# USBLCD_driver.net
KiCad netlist of a schematic drawn in Altium Designer
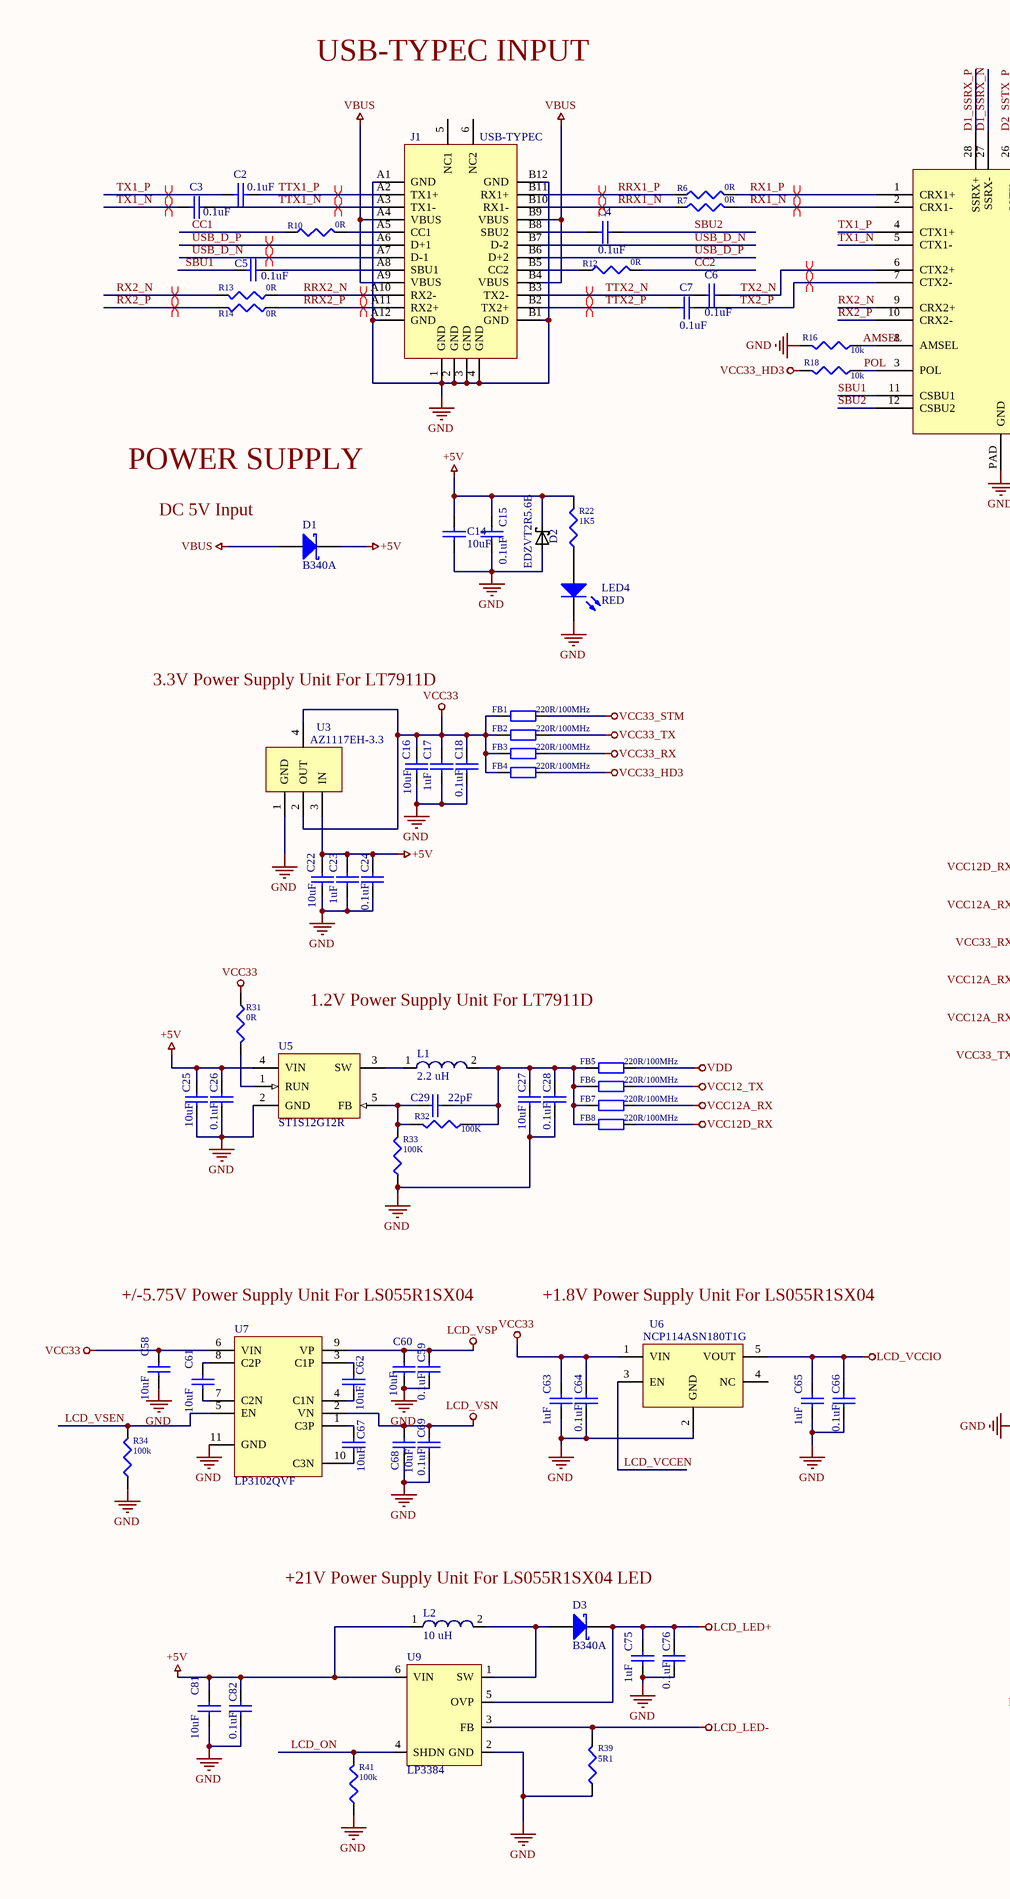
[diagram p0: USBLCD_driver.SchDoc, left]
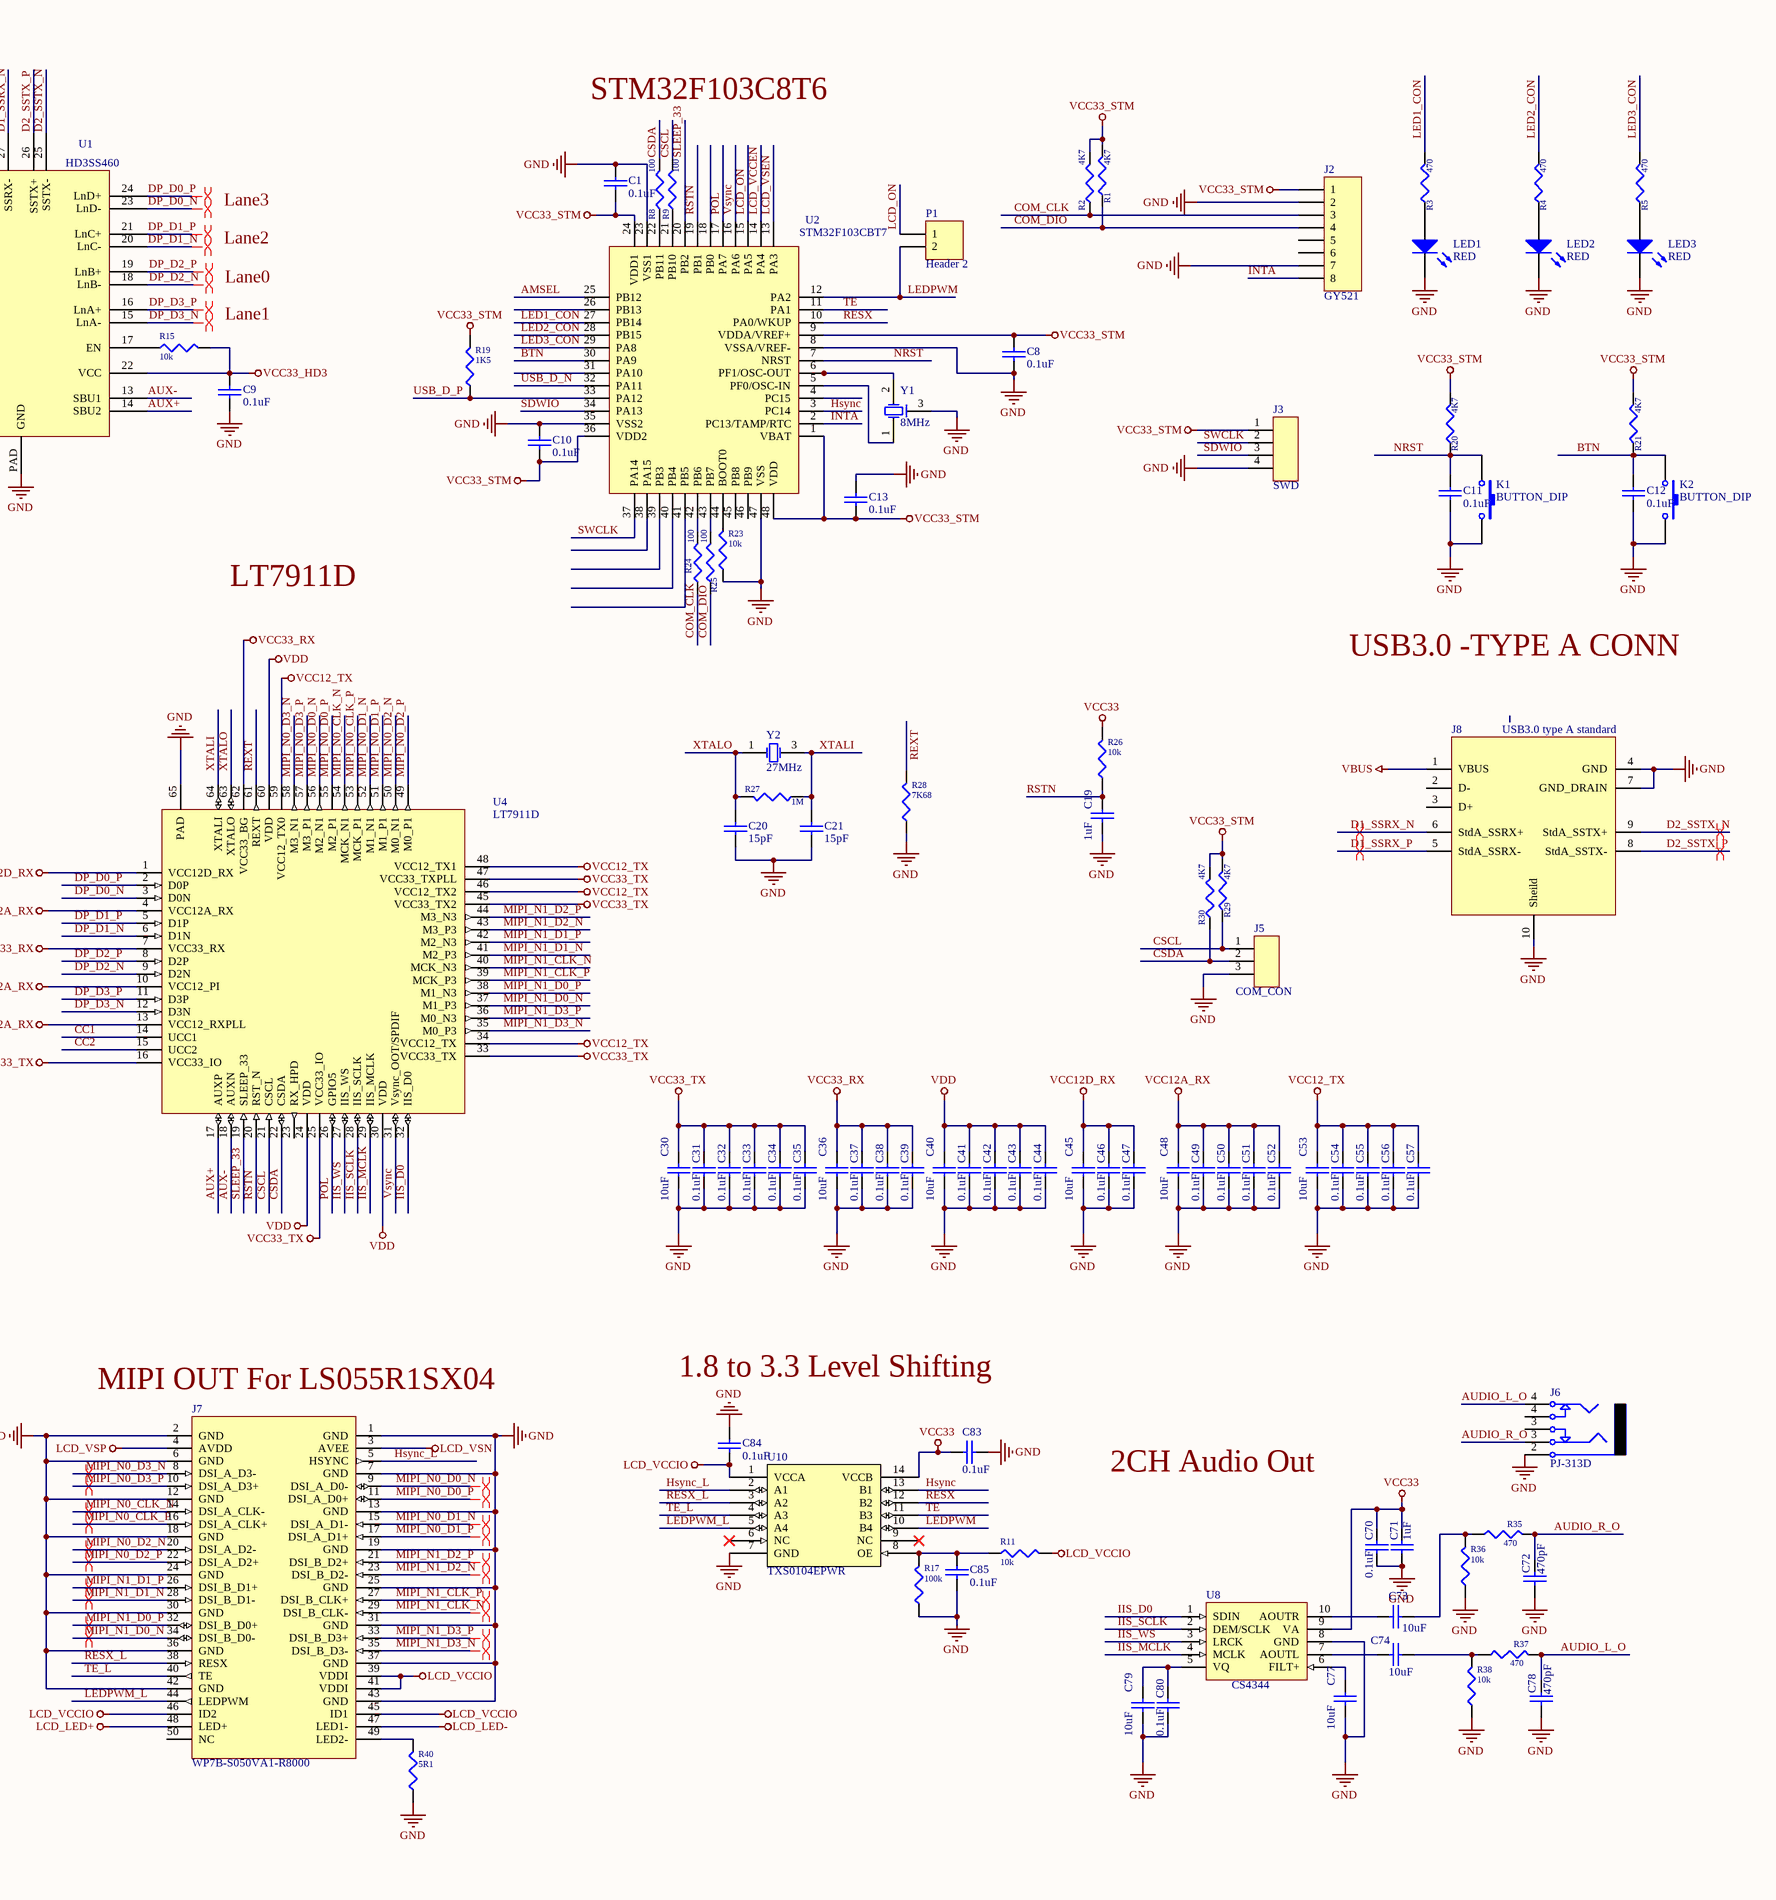
[diagram p1: USBLCD_driver.SchDoc, right]

(export (version "E")
  (design (tool "Eeschema 10.0.6"))
  (components
    (comp (ref "C1")
      (value "0.1uF")
      (footprint "CAPACITOR_SMD_0402")
      (description "CAP CER 0.1UF 16V X7R 0402")
      (fields
        (field (name "MANUFACTURER") "Murata Electronics North America")
        (field (name "MANUFACTURER PART NUMBER") "GRM155R71C104KA88D")
      )
      (libsource (lib "Maxium Referance Library for Watch") (part "CAP_0402_100n"))
    )
    (comp (ref "C2")
      (value "0.1uF")
      (footprint "CAPACITOR_SMD_0201")
      (description "CAP CER 0.1UF 10V X5R 0201")
      (fields
        (field (name "MANUFACTURER") "Murata Electronics North America")
        (field (name "MANUFACTURER PART NUMBER") "GRM033R61A104KE15D")
      )
      (libsource (lib "Maxium Referance Library for Watch") (part "CAP_0201_100n"))
    )
    (comp (ref "C3")
      (value "0.1uF")
      (footprint "CAPACITOR_SMD_0201")
      (description "CAP CER 0.1UF 10V X5R 0201")
      (fields
        (field (name "MANUFACTURER") "Murata Electronics North America")
        (field (name "MANUFACTURER PART NUMBER") "GRM033R61A104KE15D")
      )
      (libsource (lib "Maxium Referance Library for Watch") (part "CAP_0201_100n"))
    )
    (comp (ref "C4")
      (value "0.1uF")
      (footprint "CAPACITOR_SMD_0201")
      (description "CAP CER 0.1UF 10V X5R 0201")
      (fields
        (field (name "MANUFACTURER") "Murata Electronics North America")
        (field (name "MANUFACTURER PART NUMBER") "GRM033R61A104KE15D")
      )
      (libsource (lib "Maxium Referance Library for Watch") (part "CAP_0201_100n"))
    )
    (comp (ref "C5")
      (value "0.1uF")
      (footprint "CAPACITOR_SMD_0201")
      (description "CAP CER 0.1UF 10V X5R 0201")
      (fields
        (field (name "MANUFACTURER") "Murata Electronics North America")
        (field (name "MANUFACTURER PART NUMBER") "GRM033R61A104KE15D")
      )
      (libsource (lib "Maxium Referance Library for Watch") (part "CAP_0201_100n"))
    )
    (comp (ref "C6")
      (value "0.1uF")
      (footprint "CAPACITOR_SMD_0201")
      (description "CAP CER 0.1UF 10V X5R 0201")
      (fields
        (field (name "MANUFACTURER") "Murata Electronics North America")
        (field (name "MANUFACTURER PART NUMBER") "GRM033R61A104KE15D")
      )
      (libsource (lib "Maxium Referance Library for Watch") (part "CAP_0201_100n"))
    )
    (comp (ref "C7")
      (value "0.1uF")
      (footprint "CAPACITOR_SMD_0201")
      (description "CAP CER 0.1UF 10V X5R 0201")
      (fields
        (field (name "MANUFACTURER") "Murata Electronics North America")
        (field (name "MANUFACTURER PART NUMBER") "GRM033R61A104KE15D")
      )
      (libsource (lib "Maxium Referance Library for Watch") (part "CAP_0201_100n"))
    )
    (comp (ref "C8")
      (value "0.1uF")
      (footprint "CAPACITOR_SMD_0402")
      (description "CAP CER 0.1UF 16V X7R 0402")
      (fields
        (field (name "MANUFACTURER") "Murata Electronics North America")
        (field (name "MANUFACTURER PART NUMBER") "GRM155R71C104KA88D")
      )
      (libsource (lib "Maxium Referance Library for Watch") (part "CAP_0402_100n"))
    )
    (comp (ref "C9")
      (value "0.1uF")
      (footprint "CAPACITOR_SMD_0402")
      (description "CAP CER 0.1UF 16V X7R 0402")
      (fields
        (field (name "MANUFACTURER") "Murata Electronics North America")
        (field (name "MANUFACTURER PART NUMBER") "GRM155R71C104KA88D")
      )
      (libsource (lib "Maxium Referance Library for Watch") (part "CAP_0402_100n"))
    )
    (comp (ref "C10")
      (value "0.1uF")
      (footprint "CAPACITOR_SMD_0402")
      (description "CAP CER 0.1UF 16V X7R 0402")
      (fields
        (field (name "MANUFACTURER") "Murata Electronics North America")
        (field (name "MANUFACTURER PART NUMBER") "GRM155R71C104KA88D")
      )
      (libsource (lib "Maxium Referance Library for Watch") (part "CAP_0402_100n"))
    )
    (comp (ref "C11")
      (value "0.1uF")
      (footprint "CAPACITOR_SMD_0402")
      (description "CAP CER 0.1UF 16V X7R 0402")
      (fields
        (field (name "MANUFACTURER") "Murata Electronics North America")
        (field (name "MANUFACTURER PART NUMBER") "GRM155R71C104KA88D")
      )
      (libsource (lib "Maxium Referance Library for Watch") (part "CAP_0402_100n"))
    )
    (comp (ref "C12")
      (value "0.1uF")
      (footprint "CAPACITOR_SMD_0402")
      (description "CAP CER 0.1UF 16V X7R 0402")
      (fields
        (field (name "MANUFACTURER") "Murata Electronics North America")
        (field (name "MANUFACTURER PART NUMBER") "GRM155R71C104KA88D")
      )
      (libsource (lib "Maxium Referance Library for Watch") (part "CAP_0402_100n"))
    )
    (comp (ref "C13")
      (value "0.1uF")
      (footprint "CAPACITOR_SMD_0402")
      (description "CAP CER 0.1UF 16V X7R 0402")
      (fields
        (field (name "MANUFACTURER") "Murata Electronics North America")
        (field (name "MANUFACTURER PART NUMBER") "GRM155R71C104KA88D")
      )
      (libsource (lib "Maxium Referance Library for Watch") (part "CAP_0402_100n"))
    )
    (comp (ref "C14")
      (value "10uF")
      (footprint "CAPACITOR_SMD_0603")
      (description "CAP CER 1UF 16V X5R 0603")
      (fields
        (field (name "MANUFACTURER") "Murata Electronics North America")
        (field (name "MANUFACTURER PART NUMBER") "GRM188R61C105KA12D")
      )
      (libsource (lib "Maxium Referance Library for Watch") (part "CAP_0603_1u"))
    )
    (comp (ref "C15")
      (value "0.1uF")
      (footprint "CAPACITOR_SMD_0402")
      (description "CAP CER 0.1UF 16V X7R 0402")
      (fields
        (field (name "MANUFACTURER") "Murata Electronics North America")
        (field (name "MANUFACTURER PART NUMBER") "GRM155R71C104KA88D")
      )
      (libsource (lib "Maxium Referance Library for Watch") (part "CAP_0402_100n"))
    )
    (comp (ref "C16")
      (value "10uF")
      (footprint "CAPACITOR_SMD_0603")
      (description "CAP CER 1UF 16V X5R 0603")
      (fields
        (field (name "MANUFACTURER") "Murata Electronics North America")
        (field (name "MANUFACTURER PART NUMBER") "GRM188R61C105KA12D")
      )
      (libsource (lib "Maxium Referance Library for Watch") (part "CAP_0603_1u"))
    )
    (comp (ref "C17")
      (value "1uF")
      (footprint "CAPACITOR_SMD_0402")
      (description "CAP CER 10UF 4V X5R 0402")
      (fields
        (field (name "MANUFACTURER") "Murata Electronics North America")
        (field (name "MANUFACTURER PART NUMBER") "GRM155R60G106ME44D")
      )
      (libsource (lib "Maxium Referance Library for Watch") (part "CAP_0402_10u"))
    )
    (comp (ref "C18")
      (value "0.1uF")
      (footprint "CAPACITOR_SMD_0402")
      (description "CAP CER 0.1UF 16V X7R 0402")
      (fields
        (field (name "MANUFACTURER") "Murata Electronics North America")
        (field (name "MANUFACTURER PART NUMBER") "GRM155R71C104KA88D")
      )
      (libsource (lib "Maxium Referance Library for Watch") (part "CAP_0402_100n"))
    )
    (comp (ref "C19")
      (value "1uF")
      (footprint "CAPACITOR_SMD_0402")
      (description "CAP CER 10UF 4V X5R 0402")
      (fields
        (field (name "MANUFACTURER") "Murata Electronics North America")
        (field (name "MANUFACTURER PART NUMBER") "GRM155R60G106ME44D")
      )
      (libsource (lib "Maxium Referance Library for Watch") (part "CAP_0402_10u"))
    )
    (comp (ref "C20")
      (value "15pF")
      (footprint "CAPACITOR_SMD_0402")
      (description "CAP CER 10UF 4V X5R 0402")
      (fields
        (field (name "MANUFACTURER") "Murata Electronics North America")
        (field (name "MANUFACTURER PART NUMBER") "GRM155R60G106ME44D")
      )
      (libsource (lib "Maxium Referance Library for Watch") (part "CAP_0402_10u"))
    )
    (comp (ref "C21")
      (value "15pF")
      (footprint "CAPACITOR_SMD_0402")
      (description "CAP CER 10UF 4V X5R 0402")
      (fields
        (field (name "MANUFACTURER") "Murata Electronics North America")
        (field (name "MANUFACTURER PART NUMBER") "GRM155R60G106ME44D")
      )
      (libsource (lib "Maxium Referance Library for Watch") (part "CAP_0402_10u"))
    )
    (comp (ref "C22")
      (value "10uF")
      (footprint "CAPACITOR_SMD_0603")
      (description "CAP CER 1UF 16V X5R 0603")
      (fields
        (field (name "MANUFACTURER") "Murata Electronics North America")
        (field (name "MANUFACTURER PART NUMBER") "GRM188R61C105KA12D")
      )
      (libsource (lib "Maxium Referance Library for Watch") (part "CAP_0603_1u"))
    )
    (comp (ref "C23")
      (value "1uF")
      (footprint "CAPACITOR_SMD_0402")
      (description "CAP CER 10UF 4V X5R 0402")
      (fields
        (field (name "MANUFACTURER") "Murata Electronics North America")
        (field (name "MANUFACTURER PART NUMBER") "GRM155R60G106ME44D")
      )
      (libsource (lib "Maxium Referance Library for Watch") (part "CAP_0402_10u"))
    )
    (comp (ref "C24")
      (value "0.1uF")
      (footprint "CAPACITOR_SMD_0402")
      (description "CAP CER 0.1UF 16V X7R 0402")
      (fields
        (field (name "MANUFACTURER") "Murata Electronics North America")
        (field (name "MANUFACTURER PART NUMBER") "GRM155R71C104KA88D")
      )
      (libsource (lib "Maxium Referance Library for Watch") (part "CAP_0402_100n"))
    )
    (comp (ref "C25")
      (value "10uF")
      (footprint "CAPACITOR_SMD_0603")
      (description "CAP CER 1UF 16V X5R 0603")
      (fields
        (field (name "MANUFACTURER") "Murata Electronics North America")
        (field (name "MANUFACTURER PART NUMBER") "GRM188R61C105KA12D")
      )
      (libsource (lib "Maxium Referance Library for Watch") (part "CAP_0603_1u"))
    )
    (comp (ref "C26")
      (value "0.1uF")
      (footprint "CAPACITOR_SMD_0402")
      (description "CAP CER 0.1UF 16V X7R 0402")
      (fields
        (field (name "MANUFACTURER") "Murata Electronics North America")
        (field (name "MANUFACTURER PART NUMBER") "GRM155R71C104KA88D")
      )
      (libsource (lib "Maxium Referance Library for Watch") (part "CAP_0402_100n"))
    )
    (comp (ref "C27")
      (value "10uF")
      (footprint "CAPACITOR_SMD_0603")
      (description "CAP CER 1UF 16V X5R 0603")
      (fields
        (field (name "MANUFACTURER") "Murata Electronics North America")
        (field (name "MANUFACTURER PART NUMBER") "GRM188R61C105KA12D")
      )
      (libsource (lib "Maxium Referance Library for Watch") (part "CAP_0603_1u"))
    )
    (comp (ref "C28")
      (value "0.1uF")
      (footprint "CAPACITOR_SMD_0402")
      (description "CAP CER 0.1UF 16V X7R 0402")
      (fields
        (field (name "MANUFACTURER") "Murata Electronics North America")
        (field (name "MANUFACTURER PART NUMBER") "GRM155R71C104KA88D")
      )
      (libsource (lib "Maxium Referance Library for Watch") (part "CAP_0402_100n"))
    )
    (comp (ref "C29")
      (value "22pF")
      (footprint "CAPACITOR_SMD_0402")
      (description "CAP CER 10UF 4V X5R 0402")
      (fields
        (field (name "MANUFACTURER") "Murata Electronics North America")
        (field (name "MANUFACTURER PART NUMBER") "GRM155R60G106ME44D")
      )
      (libsource (lib "Maxium Referance Library for Watch") (part "CAP_0402_10u"))
    )
    (comp (ref "C30")
      (value "10uF")
      (footprint "CAPACITOR_SMD_0603")
      (description "CAP CER 1UF 16V X5R 0603")
      (fields
        (field (name "MANUFACTURER") "Murata Electronics North America")
        (field (name "MANUFACTURER PART NUMBER") "GRM188R61C105KA12D")
      )
      (libsource (lib "Maxium Referance Library for Watch") (part "CAP_0603_1u"))
    )
    (comp (ref "C31")
      (value "0.1uF")
      (footprint "CAPACITOR_SMD_0402")
      (description "CAP CER 0.1UF 16V X7R 0402")
      (fields
        (field (name "MANUFACTURER") "Murata Electronics North America")
        (field (name "MANUFACTURER PART NUMBER") "GRM155R71C104KA88D")
      )
      (libsource (lib "Maxium Referance Library for Watch") (part "CAP_0402_100n"))
    )
    (comp (ref "C32")
      (value "0.1uF")
      (footprint "CAPACITOR_SMD_0402")
      (description "CAP CER 0.1UF 16V X7R 0402")
      (fields
        (field (name "MANUFACTURER") "Murata Electronics North America")
        (field (name "MANUFACTURER PART NUMBER") "GRM155R71C104KA88D")
      )
      (libsource (lib "Maxium Referance Library for Watch") (part "CAP_0402_100n"))
    )
    (comp (ref "C33")
      (value "0.1uF")
      (footprint "CAPACITOR_SMD_0402")
      (description "CAP CER 0.1UF 16V X7R 0402")
      (fields
        (field (name "MANUFACTURER") "Murata Electronics North America")
        (field (name "MANUFACTURER PART NUMBER") "GRM155R71C104KA88D")
      )
      (libsource (lib "Maxium Referance Library for Watch") (part "CAP_0402_100n"))
    )
    (comp (ref "C34")
      (value "0.1uF")
      (footprint "CAPACITOR_SMD_0402")
      (description "CAP CER 0.1UF 16V X7R 0402")
      (fields
        (field (name "MANUFACTURER") "Murata Electronics North America")
        (field (name "MANUFACTURER PART NUMBER") "GRM155R71C104KA88D")
      )
      (libsource (lib "Maxium Referance Library for Watch") (part "CAP_0402_100n"))
    )
    (comp (ref "C35")
      (value "0.1uF")
      (footprint "CAPACITOR_SMD_0402")
      (description "CAP CER 0.1UF 16V X7R 0402")
      (fields
        (field (name "MANUFACTURER") "Murata Electronics North America")
        (field (name "MANUFACTURER PART NUMBER") "GRM155R71C104KA88D")
      )
      (libsource (lib "Maxium Referance Library for Watch") (part "CAP_0402_100n"))
    )
    (comp (ref "C36")
      (value "10uF")
      (footprint "CAPACITOR_SMD_0603")
      (description "CAP CER 1UF 16V X5R 0603")
      (fields
        (field (name "MANUFACTURER") "Murata Electronics North America")
        (field (name "MANUFACTURER PART NUMBER") "GRM188R61C105KA12D")
      )
      (libsource (lib "Maxium Referance Library for Watch") (part "CAP_0603_1u"))
    )
    (comp (ref "C37")
      (value "0.1uF")
      (footprint "CAPACITOR_SMD_0402")
      (description "CAP CER 0.1UF 16V X7R 0402")
      (fields
        (field (name "MANUFACTURER") "Murata Electronics North America")
        (field (name "MANUFACTURER PART NUMBER") "GRM155R71C104KA88D")
      )
      (libsource (lib "Maxium Referance Library for Watch") (part "CAP_0402_100n"))
    )
    (comp (ref "C38")
      (value "0.1uF")
      (footprint "CAPACITOR_SMD_0402")
      (description "CAP CER 0.1UF 16V X7R 0402")
      (fields
        (field (name "MANUFACTURER") "Murata Electronics North America")
        (field (name "MANUFACTURER PART NUMBER") "GRM155R71C104KA88D")
      )
      (libsource (lib "Maxium Referance Library for Watch") (part "CAP_0402_100n"))
    )
    (comp (ref "C39")
      (value "0.1uF")
      (footprint "CAPACITOR_SMD_0402")
      (description "CAP CER 0.1UF 16V X7R 0402")
      (fields
        (field (name "MANUFACTURER") "Murata Electronics North America")
        (field (name "MANUFACTURER PART NUMBER") "GRM155R71C104KA88D")
      )
      (libsource (lib "Maxium Referance Library for Watch") (part "CAP_0402_100n"))
    )
    (comp (ref "C40")
      (value "10uF")
      (footprint "CAPACITOR_SMD_0603")
      (description "CAP CER 1UF 16V X5R 0603")
      (fields
        (field (name "MANUFACTURER") "Murata Electronics North America")
        (field (name "MANUFACTURER PART NUMBER") "GRM188R61C105KA12D")
      )
      (libsource (lib "Maxium Referance Library for Watch") (part "CAP_0603_1u"))
    )
    (comp (ref "C41")
      (value "0.1uF")
      (footprint "CAPACITOR_SMD_0402")
      (description "CAP CER 0.1UF 16V X7R 0402")
      (fields
        (field (name "MANUFACTURER") "Murata Electronics North America")
        (field (name "MANUFACTURER PART NUMBER") "GRM155R71C104KA88D")
      )
      (libsource (lib "Maxium Referance Library for Watch") (part "CAP_0402_100n"))
    )
    (comp (ref "C42")
      (value "0.1uF")
      (footprint "CAPACITOR_SMD_0402")
      (description "CAP CER 0.1UF 16V X7R 0402")
      (fields
        (field (name "MANUFACTURER") "Murata Electronics North America")
        (field (name "MANUFACTURER PART NUMBER") "GRM155R71C104KA88D")
      )
      (libsource (lib "Maxium Referance Library for Watch") (part "CAP_0402_100n"))
    )
    (comp (ref "C43")
      (value "0.1uF")
      (footprint "CAPACITOR_SMD_0402")
      (description "CAP CER 0.1UF 16V X7R 0402")
      (fields
        (field (name "MANUFACTURER") "Murata Electronics North America")
        (field (name "MANUFACTURER PART NUMBER") "GRM155R71C104KA88D")
      )
      (libsource (lib "Maxium Referance Library for Watch") (part "CAP_0402_100n"))
    )
    (comp (ref "C44")
      (value "0.1uF")
      (footprint "CAPACITOR_SMD_0402")
      (description "CAP CER 0.1UF 16V X7R 0402")
      (fields
        (field (name "MANUFACTURER") "Murata Electronics North America")
        (field (name "MANUFACTURER PART NUMBER") "GRM155R71C104KA88D")
      )
      (libsource (lib "Maxium Referance Library for Watch") (part "CAP_0402_100n"))
    )
    (comp (ref "C45")
      (value "10uF")
      (footprint "CAPACITOR_SMD_0603")
      (description "CAP CER 1UF 16V X5R 0603")
      (fields
        (field (name "MANUFACTURER") "Murata Electronics North America")
        (field (name "MANUFACTURER PART NUMBER") "GRM188R61C105KA12D")
      )
      (libsource (lib "Maxium Referance Library for Watch") (part "CAP_0603_1u"))
    )
    (comp (ref "C46")
      (value "0.1uF")
      (footprint "CAPACITOR_SMD_0402")
      (description "CAP CER 0.1UF 16V X7R 0402")
      (fields
        (field (name "MANUFACTURER") "Murata Electronics North America")
        (field (name "MANUFACTURER PART NUMBER") "GRM155R71C104KA88D")
      )
      (libsource (lib "Maxium Referance Library for Watch") (part "CAP_0402_100n"))
    )
    (comp (ref "C47")
      (value "0.1uF")
      (footprint "CAPACITOR_SMD_0402")
      (description "CAP CER 0.1UF 16V X7R 0402")
      (fields
        (field (name "MANUFACTURER") "Murata Electronics North America")
        (field (name "MANUFACTURER PART NUMBER") "GRM155R71C104KA88D")
      )
      (libsource (lib "Maxium Referance Library for Watch") (part "CAP_0402_100n"))
    )
    (comp (ref "C48")
      (value "10uF")
      (footprint "CAPACITOR_SMD_0603")
      (description "CAP CER 1UF 16V X5R 0603")
      (fields
        (field (name "MANUFACTURER") "Murata Electronics North America")
        (field (name "MANUFACTURER PART NUMBER") "GRM188R61C105KA12D")
      )
      (libsource (lib "Maxium Referance Library for Watch") (part "CAP_0603_1u"))
    )
    (comp (ref "C49")
      (value "0.1uF")
      (footprint "CAPACITOR_SMD_0402")
      (description "CAP CER 0.1UF 16V X7R 0402")
      (fields
        (field (name "MANUFACTURER") "Murata Electronics North America")
        (field (name "MANUFACTURER PART NUMBER") "GRM155R71C104KA88D")
      )
      (libsource (lib "Maxium Referance Library for Watch") (part "CAP_0402_100n"))
    )
    (comp (ref "C50")
      (value "0.1uF")
      (footprint "CAPACITOR_SMD_0402")
      (description "CAP CER 0.1UF 16V X7R 0402")
      (fields
        (field (name "MANUFACTURER") "Murata Electronics North America")
        (field (name "MANUFACTURER PART NUMBER") "GRM155R71C104KA88D")
      )
      (libsource (lib "Maxium Referance Library for Watch") (part "CAP_0402_100n"))
    )
    (comp (ref "C51")
      (value "0.1uF")
      (footprint "CAPACITOR_SMD_0402")
      (description "CAP CER 0.1UF 16V X7R 0402")
      (fields
        (field (name "MANUFACTURER") "Murata Electronics North America")
        (field (name "MANUFACTURER PART NUMBER") "GRM155R71C104KA88D")
      )
      (libsource (lib "Maxium Referance Library for Watch") (part "CAP_0402_100n"))
    )
    (comp (ref "C52")
      (value "0.1uF")
      (footprint "CAPACITOR_SMD_0402")
      (description "CAP CER 0.1UF 16V X7R 0402")
      (fields
        (field (name "MANUFACTURER") "Murata Electronics North America")
        (field (name "MANUFACTURER PART NUMBER") "GRM155R71C104KA88D")
      )
      (libsource (lib "Maxium Referance Library for Watch") (part "CAP_0402_100n"))
    )
    (comp (ref "C53")
      (value "10uF")
      (footprint "CAPACITOR_SMD_0603")
      (description "CAP CER 1UF 16V X5R 0603")
      (fields
        (field (name "MANUFACTURER") "Murata Electronics North America")
        (field (name "MANUFACTURER PART NUMBER") "GRM188R61C105KA12D")
      )
      (libsource (lib "Maxium Referance Library for Watch") (part "CAP_0603_1u"))
    )
    (comp (ref "C54")
      (value "0.1uF")
      (footprint "CAPACITOR_SMD_0402")
      (description "CAP CER 0.1UF 16V X7R 0402")
      (fields
        (field (name "MANUFACTURER") "Murata Electronics North America")
        (field (name "MANUFACTURER PART NUMBER") "GRM155R71C104KA88D")
      )
      (libsource (lib "Maxium Referance Library for Watch") (part "CAP_0402_100n"))
    )
    (comp (ref "C55")
      (value "0.1uF")
      (footprint "CAPACITOR_SMD_0402")
      (description "CAP CER 0.1UF 16V X7R 0402")
      (fields
        (field (name "MANUFACTURER") "Murata Electronics North America")
        (field (name "MANUFACTURER PART NUMBER") "GRM155R71C104KA88D")
      )
      (libsource (lib "Maxium Referance Library for Watch") (part "CAP_0402_100n"))
    )
    (comp (ref "C56")
      (value "0.1uF")
      (footprint "CAPACITOR_SMD_0402")
      (description "CAP CER 0.1UF 16V X7R 0402")
      (fields
        (field (name "MANUFACTURER") "Murata Electronics North America")
        (field (name "MANUFACTURER PART NUMBER") "GRM155R71C104KA88D")
      )
      (libsource (lib "Maxium Referance Library for Watch") (part "CAP_0402_100n"))
    )
    (comp (ref "C57")
      (value "0.1uF")
      (footprint "CAPACITOR_SMD_0402")
      (description "CAP CER 0.1UF 16V X7R 0402")
      (fields
        (field (name "MANUFACTURER") "Murata Electronics North America")
        (field (name "MANUFACTURER PART NUMBER") "GRM155R71C104KA88D")
      )
      (libsource (lib "Maxium Referance Library for Watch") (part "CAP_0402_100n"))
    )
    (comp (ref "C58")
      (value "10uF")
      (footprint "CAPACITOR_SMD_0603")
      (description "CAP CER 1UF 16V X5R 0603")
      (fields
        (field (name "MANUFACTURER") "Murata Electronics North America")
        (field (name "MANUFACTURER PART NUMBER") "GRM188R61C105KA12D")
      )
      (libsource (lib "Maxium Referance Library for Watch") (part "CAP_0603_1u"))
    )
    (comp (ref "C59")
      (value "0.1uF")
      (footprint "CAPACITOR_SMD_0402")
      (description "CAP CER 0.1UF 16V X7R 0402")
      (fields
        (field (name "MANUFACTURER") "Murata Electronics North America")
        (field (name "MANUFACTURER PART NUMBER") "GRM155R71C104KA88D")
      )
      (libsource (lib "Maxium Referance Library for Watch") (part "CAP_0402_100n"))
    )
    (comp (ref "C60")
      (value "10uF")
      (footprint "CAPACITOR_SMD_0603")
      (description "CAP CER 1UF 16V X5R 0603")
      (fields
        (field (name "MANUFACTURER") "Murata Electronics North America")
        (field (name "MANUFACTURER PART NUMBER") "GRM188R61C105KA12D")
      )
      (libsource (lib "Maxium Referance Library for Watch") (part "CAP_0603_1u"))
    )
    (comp (ref "C61")
      (value "10uF")
      (footprint "CAPACITOR_SMD_0603")
      (description "CAP CER 1UF 16V X5R 0603")
      (fields
        (field (name "MANUFACTURER") "Murata Electronics North America")
        (field (name "MANUFACTURER PART NUMBER") "GRM188R61C105KA12D")
      )
      (libsource (lib "Maxium Referance Library for Watch") (part "CAP_0603_1u"))
    )
    (comp (ref "C62")
      (value "10uF")
      (footprint "CAPACITOR_SMD_0603")
      (description "CAP CER 1UF 16V X5R 0603")
      (fields
        (field (name "MANUFACTURER") "Murata Electronics North America")
        (field (name "MANUFACTURER PART NUMBER") "GRM188R61C105KA12D")
      )
      (libsource (lib "Maxium Referance Library for Watch") (part "CAP_0603_1u"))
    )
    (comp (ref "C63")
      (value "1uF")
      (footprint "CAPACITOR_SMD_0402")
      (description "CAP CER 10UF 4V X5R 0402")
      (fields
        (field (name "MANUFACTURER") "Murata Electronics North America")
        (field (name "MANUFACTURER PART NUMBER") "GRM155R60G106ME44D")
      )
      (libsource (lib "Maxium Referance Library for Watch") (part "CAP_0402_10u"))
    )
    (comp (ref "C64")
      (value "0.1uF")
      (footprint "CAPACITOR_SMD_0402")
      (description "CAP CER 0.1UF 16V X7R 0402")
      (fields
        (field (name "MANUFACTURER") "Murata Electronics North America")
        (field (name "MANUFACTURER PART NUMBER") "GRM155R71C104KA88D")
      )
      (libsource (lib "Maxium Referance Library for Watch") (part "CAP_0402_100n"))
    )
    (comp (ref "C65")
      (value "1uF")
      (footprint "CAPACITOR_SMD_0402")
      (description "CAP CER 10UF 4V X5R 0402")
      (fields
        (field (name "MANUFACTURER") "Murata Electronics North America")
        (field (name "MANUFACTURER PART NUMBER") "GRM155R60G106ME44D")
      )
      (libsource (lib "Maxium Referance Library for Watch") (part "CAP_0402_10u"))
    )
    (comp (ref "C66")
      (value "0.1uF")
      (footprint "CAPACITOR_SMD_0402")
      (description "CAP CER 0.1UF 16V X7R 0402")
      (fields
        (field (name "MANUFACTURER") "Murata Electronics North America")
        (field (name "MANUFACTURER PART NUMBER") "GRM155R71C104KA88D")
      )
      (libsource (lib "Maxium Referance Library for Watch") (part "CAP_0402_100n"))
    )
    (comp (ref "C67")
      (value "10uF")
      (footprint "CAPACITOR_SMD_0603")
      (description "CAP CER 1UF 16V X5R 0603")
      (fields
        (field (name "MANUFACTURER") "Murata Electronics North America")
        (field (name "MANUFACTURER PART NUMBER") "GRM188R61C105KA12D")
      )
      (libsource (lib "Maxium Referance Library for Watch") (part "CAP_0603_1u"))
    )
    (comp (ref "C68")
      (value "10uF")
      (footprint "CAPACITOR_SMD_0603")
      (description "CAP CER 1UF 16V X5R 0603")
      (fields
        (field (name "MANUFACTURER") "Murata Electronics North America")
        (field (name "MANUFACTURER PART NUMBER") "GRM188R61C105KA12D")
      )
      (libsource (lib "Maxium Referance Library for Watch") (part "CAP_0603_1u"))
    )
    (comp (ref "C69")
      (value "0.1uF")
      (footprint "CAPACITOR_SMD_0402")
      (description "CAP CER 0.1UF 16V X7R 0402")
      (fields
        (field (name "MANUFACTURER") "Murata Electronics North America")
        (field (name "MANUFACTURER PART NUMBER") "GRM155R71C104KA88D")
      )
      (libsource (lib "Maxium Referance Library for Watch") (part "CAP_0402_100n"))
    )
    (comp (ref "C70")
      (value "0.1uF")
      (footprint "CAPACITOR_SMD_0402")
      (description "CAP CER 0.1UF 16V X7R 0402")
      (fields
        (field (name "MANUFACTURER") "Murata Electronics North America")
        (field (name "MANUFACTURER PART NUMBER") "GRM155R71C104KA88D")
      )
      (libsource (lib "Maxium Referance Library for Watch") (part "CAP_0402_100n"))
    )
    (comp (ref "C71")
      (value "1uF")
      (footprint "CAPACITOR_SMD_0402")
      (description "CAP CER 10UF 4V X5R 0402")
      (fields
        (field (name "MANUFACTURER") "Murata Electronics North America")
        (field (name "MANUFACTURER PART NUMBER") "GRM155R60G106ME44D")
      )
      (libsource (lib "Maxium Referance Library for Watch") (part "CAP_0402_10u"))
    )
    (comp (ref "C72")
      (value "470pF")
      (footprint "CAPACITOR_SMD_0402")
      (description "CAP CER 10UF 4V X5R 0402")
      (fields
        (field (name "MANUFACTURER") "Murata Electronics North America")
        (field (name "MANUFACTURER PART NUMBER") "GRM155R60G106ME44D")
      )
      (libsource (lib "Maxium Referance Library for Watch") (part "CAP_0402_10u"))
    )
    (comp (ref "C73")
      (value "10uF")
      (footprint "CAPACITOR_SMD_0603")
      (description "CAP CER 1UF 16V X5R 0603")
      (fields
        (field (name "MANUFACTURER") "Murata Electronics North America")
        (field (name "MANUFACTURER PART NUMBER") "GRM188R61C105KA12D")
      )
      (libsource (lib "Maxium Referance Library for Watch") (part "CAP_0603_1u"))
    )
    (comp (ref "C74")
      (value "10uF")
      (footprint "CAPACITOR_SMD_0603")
      (description "CAP CER 1UF 16V X5R 0603")
      (fields
        (field (name "MANUFACTURER") "Murata Electronics North America")
        (field (name "MANUFACTURER PART NUMBER") "GRM188R61C105KA12D")
      )
      (libsource (lib "Maxium Referance Library for Watch") (part "CAP_0603_1u"))
    )
    (comp (ref "C75")
      (value "1uF")
      (footprint "CAPACITOR_SMD_0402")
      (description "CAP CER 10UF 4V X5R 0402")
      (fields
        (field (name "MANUFACTURER") "Murata Electronics North America")
        (field (name "MANUFACTURER PART NUMBER") "GRM155R60G106ME44D")
      )
      (libsource (lib "Maxium Referance Library for Watch") (part "CAP_0402_10u"))
    )
    (comp (ref "C76")
      (value "0.1uF")
      (footprint "CAPACITOR_SMD_0402")
      (description "CAP CER 0.1UF 16V X7R 0402")
      (fields
        (field (name "MANUFACTURER") "Murata Electronics North America")
        (field (name "MANUFACTURER PART NUMBER") "GRM155R71C104KA88D")
      )
      (libsource (lib "Maxium Referance Library for Watch") (part "CAP_0402_100n"))
    )
    (comp (ref "C77")
      (value "10uF")
      (footprint "CAPACITOR_SMD_0603")
      (description "CAP CER 1UF 16V X5R 0603")
      (fields
        (field (name "MANUFACTURER") "Murata Electronics North America")
        (field (name "MANUFACTURER PART NUMBER") "GRM188R61C105KA12D")
      )
      (libsource (lib "Maxium Referance Library for Watch") (part "CAP_0603_1u"))
    )
    (comp (ref "C78")
      (value "470pF")
      (footprint "CAPACITOR_SMD_0402")
      (description "CAP CER 10UF 4V X5R 0402")
      (fields
        (field (name "MANUFACTURER") "Murata Electronics North America")
        (field (name "MANUFACTURER PART NUMBER") "GRM155R60G106ME44D")
      )
      (libsource (lib "Maxium Referance Library for Watch") (part "CAP_0402_10u"))
    )
    (comp (ref "C79")
      (value "10uF")
      (footprint "CAPACITOR_SMD_0603")
      (description "CAP CER 1UF 16V X5R 0603")
      (fields
        (field (name "MANUFACTURER") "Murata Electronics North America")
        (field (name "MANUFACTURER PART NUMBER") "GRM188R61C105KA12D")
      )
      (libsource (lib "Maxium Referance Library for Watch") (part "CAP_0603_1u"))
    )
    (comp (ref "C80")
      (value "0.1uF")
      (footprint "CAPACITOR_SMD_0402")
      (description "CAP CER 0.1UF 16V X7R 0402")
      (fields
        (field (name "MANUFACTURER") "Murata Electronics North America")
        (field (name "MANUFACTURER PART NUMBER") "GRM155R71C104KA88D")
      )
      (libsource (lib "Maxium Referance Library for Watch") (part "CAP_0402_100n"))
    )
    (comp (ref "C81")
      (value "10uF")
      (footprint "CAPACITOR_SMD_0603")
      (description "CAP CER 1UF 16V X5R 0603")
      (fields
        (field (name "MANUFACTURER") "Murata Electronics North America")
        (field (name "MANUFACTURER PART NUMBER") "GRM188R61C105KA12D")
      )
      (libsource (lib "Maxium Referance Library for Watch") (part "CAP_0603_1u"))
    )
    (comp (ref "C82")
      (value "0.1uF")
      (footprint "CAPACITOR_SMD_0402")
      (description "CAP CER 0.1UF 16V X7R 0402")
      (fields
        (field (name "MANUFACTURER") "Murata Electronics North America")
        (field (name "MANUFACTURER PART NUMBER") "GRM155R71C104KA88D")
      )
      (libsource (lib "Maxium Referance Library for Watch") (part "CAP_0402_100n"))
    )
    (comp (ref "C83")
      (value "0.1uF")
      (footprint "CAPACITOR_SMD_0402")
      (description "CAP CER 0.1UF 16V X7R 0402")
      (fields
        (field (name "MANUFACTURER") "Murata Electronics North America")
        (field (name "MANUFACTURER PART NUMBER") "GRM155R71C104KA88D")
      )
      (libsource (lib "Maxium Referance Library for Watch") (part "CAP_0402_100n"))
    )
    (comp (ref "C84")
      (value "0.1uF")
      (footprint "CAPACITOR_SMD_0402")
      (description "CAP CER 0.1UF 16V X7R 0402")
      (fields
        (field (name "MANUFACTURER") "Murata Electronics North America")
        (field (name "MANUFACTURER PART NUMBER") "GRM155R71C104KA88D")
      )
      (libsource (lib "Maxium Referance Library for Watch") (part "CAP_0402_100n"))
    )
    (comp (ref "C85")
      (value "0.1uF")
      (footprint "CAPACITOR_SMD_0402")
      (description "CAP CER 0.1UF 16V X7R 0402")
      (fields
        (field (name "MANUFACTURER") "Murata Electronics North America")
        (field (name "MANUFACTURER PART NUMBER") "GRM155R71C104KA88D")
      )
      (libsource (lib "Maxium Referance Library for Watch") (part "CAP_0402_100n"))
    )
    (comp (ref "D1")
      (value "B340A")
      (footprint "DO-214AC")
      (description "Schottky Rectifier")
      (fields (field (name "PUBLISHER") "Altium Limited"))
      (libsource (lib "Miscellaneous Devices") (part "Diode 10TQ035"))
    )
    (comp (ref "D2")
      (value "EDZVT2R5.6B")
      (footprint "SOD128")
      (fields (field (name "MP") "BAT46W") (field (name "MF") "Diotec"))
      (libsource (lib "MySchLib") (part "BAT46W"))
    )
    (comp (ref "D3")
      (value "B340A")
      (footprint "DO-214AC")
      (description "Schottky Rectifier")
      (fields (field (name "PUBLISHER") "Altium Limited"))
      (libsource (lib "Miscellaneous Devices") (part "Diode 10TQ035"))
    )
    (comp (ref "FB1")
      (value "220R/100MHz")
      (footprint "SMD_0603")
      (description "Ferrite Bead(0603)")
      (fields (field (name "PUBLISHER") "Altium Limited"))
      (libsource (lib "Miscellaneous Devices") (part "Res2"))
    )
    (comp (ref "FB2")
      (value "220R/100MHz")
      (footprint "SMD_0603")
      (description "Ferrite Bead(0603)")
      (fields (field (name "PUBLISHER") "Altium Limited"))
      (libsource (lib "Miscellaneous Devices") (part "Res2"))
    )
    (comp (ref "FB3")
      (value "220R/100MHz")
      (footprint "SMD_0603")
      (description "Ferrite Bead(0603)")
      (fields (field (name "PUBLISHER") "Altium Limited"))
      (libsource (lib "Miscellaneous Devices") (part "Res2"))
    )
    (comp (ref "FB4")
      (value "220R/100MHz")
      (footprint "SMD_0603")
      (description "Ferrite Bead(0603)")
      (fields (field (name "PUBLISHER") "Altium Limited"))
      (libsource (lib "Miscellaneous Devices") (part "Res2"))
    )
    (comp (ref "FB5")
      (value "220R/100MHz")
      (footprint "SMD_0603")
      (description "Ferrite Bead(0603)")
      (fields (field (name "PUBLISHER") "Altium Limited"))
      (libsource (lib "Miscellaneous Devices") (part "Res2"))
    )
    (comp (ref "FB6")
      (value "220R/100MHz")
      (footprint "SMD_0603")
      (description "Ferrite Bead(0603)")
      (fields (field (name "PUBLISHER") "Altium Limited"))
      (libsource (lib "Miscellaneous Devices") (part "Res2"))
    )
    (comp (ref "FB7")
      (value "220R/100MHz")
      (footprint "SMD_0603")
      (description "Ferrite Bead(0603)")
      (fields (field (name "PUBLISHER") "Altium Limited"))
      (libsource (lib "Miscellaneous Devices") (part "Res2"))
    )
    (comp (ref "FB8")
      (value "220R/100MHz")
      (footprint "SMD_0603")
      (description "Ferrite Bead(0603)")
      (fields (field (name "PUBLISHER") "Altium Limited"))
      (libsource (lib "Miscellaneous Devices") (part "Res2"))
    )
    (comp (ref "J1")
      (value "USB-TYPEC")
      (footprint "USB_TYPEC_RECEPTACLE_DIP")
      (description "USB-TYPE C Receptable DIP Connector")
      (libsource (lib "MySchLib") (part "USB-TYPEC"))
    )
    (comp (ref "J2")
      (value "GY521")
      (footprint "HDR1X8")
      (description "Header, 8-Pin")
      (fields (field (name "PUBLISHER") "Altium Limited"))
      (libsource (lib "Miscellaneous Connectors") (part "Header 8"))
    )
    (comp (ref "J3")
      (value "SWD")
      (footprint "Header-Female-2.54*4")
      (libsource (lib "MySchLib") (part "4PinConnector"))
    )
    (comp (ref "J5")
      (value "COM_CON")
      (footprint "Header-Female-2.54*3")
      (libsource (lib "MySchLib") (part "3PinConnector"))
    )
    (comp (ref "J6")
      (value "PJ-313D")
      (footprint "WQP-PJ313D")
      (description "Connector, 3.5mm Stereo Audio Socket, Black")
      (libsource (lib "MySchLib") (part "WPQ-PJ313D"))
    )
    (comp (ref "J7")
      (value "WP7B-S050VA1-R8000")
      (footprint "WP7B-S050VA1-R500")
      (description "WP7B-S050VA1-R8000\r\nLCD Connector for LS055R1SX04")
      (libsource (lib "MySchLib") (part "LS055R1SX04"))
    )
    (comp (ref "J8")
      (value "USB3.0 type A standard")
      (footprint "USB type A female connector")
      (description "9Pin DIP USB3.0 type A female Connector")
      (libsource (lib "MySchLib") (part "USB3.0 type A standard"))
    )
    (comp (ref "K1")
      (value "BUTTON_DIP")
      (footprint "Push button_mini(2 pin)")
      (description "2 Pin Mini Push Button Switch")
      (fields (field (name "PUBLISHER") "Altium Limited"))
      (libsource (lib "Miscellaneous Devices") (part "SW-PB"))
    )
    (comp (ref "K2")
      (value "BUTTON_DIP")
      (footprint "Push button_mini(2 pin)")
      (description "2 Pin Mini Push Button Switch")
      (fields (field (name "PUBLISHER") "Altium Limited"))
      (libsource (lib "Miscellaneous Devices") (part "SW-PB"))
    )
    (comp (ref "L1")
      (value "2.2 uH")
      (footprint "WE-LQS 3015")
      (description "SMD Power Inductor, L=2.2 µH 1.5A 72mOhm")
      (fields (field (name "PARTNUMBER") "NR3015T2R2M") (field (name "MANUFACTURER") "Taiyo Yuden"))
      (libsource (lib "Altium Content Vault") (part "WE-IND-INDUCTOR-2"))
    )
    (comp (ref "L2")
      (value "10 uH")
      (footprint "WE-LQS 4018")
      (description "WE-LQS SMD Power Inductor, L=10 µH")
      (fields (field (name "PARTNUMBER") "NRS4018T100MDGJ") (field (name "MANUFACTURER") "Taiyo Yuden"))
      (libsource (lib "Altium Content Vault") (part "WE-IND-INDUCTOR-2"))
    )
    (comp (ref "LED1")
      (value "RED")
      (footprint "SMD_LED(0603)")
      (description "Typical RED GaAs LED")
      (fields (field (name "PUBLISHER") "Altium Limited"))
      (libsource (lib "Miscellaneous Devices") (part "LED1"))
    )
    (comp (ref "LED2")
      (value "RED")
      (footprint "SMD_LED(0603)")
      (description "Typical RED GaAs LED")
      (fields (field (name "PUBLISHER") "Altium Limited"))
      (libsource (lib "Miscellaneous Devices") (part "LED1"))
    )
    (comp (ref "LED3")
      (value "RED")
      (footprint "SMD_LED(0603)")
      (description "Typical RED GaAs LED")
      (fields (field (name "PUBLISHER") "Altium Limited"))
      (libsource (lib "Miscellaneous Devices") (part "LED1"))
    )
    (comp (ref "LED4")
      (value "RED")
      (footprint "SMD_LED(0603)")
      (description "Typical RED GaAs LED")
      (fields (field (name "PUBLISHER") "Altium Limited"))
      (libsource (lib "Miscellaneous Devices") (part "LED1"))
    )
    (comp (ref "P1")
      (value "Header 2")
      (footprint "HDR1X2")
      (description "Header, 2-Pin")
      (fields (field (name "PUBLISHER") "Altium Limited"))
      (libsource (lib "Miscellaneous Connectors") (part "Header 2"))
    )
    (comp (ref "R1")
      (value "4K7")
      (footprint "RESISTOR_SMD_0402")
      (description "RES SMD 3.3K OHM 1% 1/10W 0402")
      (fields
        (field (name "MANUFACTURER") "Panasonic Electronic Components")
        (field (name "MANUFACTURER PART NUMBER") "ERJ-2RKF3301X")
      )
      (libsource (lib "Maxium Referance Library for Watch") (part "RES_0402_3K3"))
    )
    (comp (ref "R2")
      (value "4K7")
      (footprint "RESISTOR_SMD_0402")
      (description "RES SMD 3.3K OHM 1% 1/10W 0402")
      (fields
        (field (name "MANUFACTURER") "Panasonic Electronic Components")
        (field (name "MANUFACTURER PART NUMBER") "ERJ-2RKF3301X")
      )
      (libsource (lib "Maxium Referance Library for Watch") (part "RES_0402_3K3"))
    )
    (comp (ref "R3")
      (value "470")
      (footprint "RESISTOR_SMD_0402")
      (description "RES SMD 3.3K OHM 1% 1/10W 0402")
      (fields
        (field (name "MANUFACTURER") "Panasonic Electronic Components")
        (field (name "MANUFACTURER PART NUMBER") "ERJ-2RKF3301X")
      )
      (libsource (lib "Maxium Referance Library for Watch") (part "RES_0402_3K3"))
    )
    (comp (ref "R4")
      (value "470")
      (footprint "RESISTOR_SMD_0402")
      (description "RES SMD 3.3K OHM 1% 1/10W 0402")
      (fields
        (field (name "MANUFACTURER") "Panasonic Electronic Components")
        (field (name "MANUFACTURER PART NUMBER") "ERJ-2RKF3301X")
      )
      (libsource (lib "Maxium Referance Library for Watch") (part "RES_0402_3K3"))
    )
    (comp (ref "R5")
      (value "470")
      (footprint "RESISTOR_SMD_0402")
      (description "RES SMD 3.3K OHM 1% 1/10W 0402")
      (fields
        (field (name "MANUFACTURER") "Panasonic Electronic Components")
        (field (name "MANUFACTURER PART NUMBER") "ERJ-2RKF3301X")
      )
      (libsource (lib "Maxium Referance Library for Watch") (part "RES_0402_3K3"))
    )
    (comp (ref "R6")
      (value "0R")
      (footprint "RESISTOR_SMD_0201")
      (description "RES SMD 10 OHM 1% 1/20W 0201")
      (fields
        (field (name "MANUFACTURER") "Panasonic Electronic Components")
        (field (name "MANUFACTURER PART NUMBER") "ERJ-1GEF10R0C")
      )
      (libsource (lib "Maxium Referance Library for Watch") (part "RES_0201_10R"))
    )
    (comp (ref "R7")
      (value "0R")
      (footprint "RESISTOR_SMD_0201")
      (description "RES SMD 10 OHM 1% 1/20W 0201")
      (fields
        (field (name "MANUFACTURER") "Panasonic Electronic Components")
        (field (name "MANUFACTURER PART NUMBER") "ERJ-1GEF10R0C")
      )
      (libsource (lib "Maxium Referance Library for Watch") (part "RES_0201_10R"))
    )
    (comp (ref "R8")
      (value "100")
      (footprint "RESISTOR_SMD_0402")
      (description "RES SMD 3.3K OHM 1% 1/10W 0402")
      (fields
        (field (name "MANUFACTURER") "Panasonic Electronic Components")
        (field (name "MANUFACTURER PART NUMBER") "ERJ-2RKF3301X")
      )
      (libsource (lib "Maxium Referance Library for Watch") (part "RES_0402_3K3"))
    )
    (comp (ref "R9")
      (value "100")
      (footprint "RESISTOR_SMD_0402")
      (description "RES SMD 3.3K OHM 1% 1/10W 0402")
      (fields
        (field (name "MANUFACTURER") "Panasonic Electronic Components")
        (field (name "MANUFACTURER PART NUMBER") "ERJ-2RKF3301X")
      )
      (libsource (lib "Maxium Referance Library for Watch") (part "RES_0402_3K3"))
    )
    (comp (ref "R10")
      (value "0R")
      (footprint "RESISTOR_SMD_0201")
      (description "RES SMD 10 OHM 1% 1/20W 0201")
      (fields
        (field (name "MANUFACTURER") "Panasonic Electronic Components")
        (field (name "MANUFACTURER PART NUMBER") "ERJ-1GEF10R0C")
      )
      (libsource (lib "Maxium Referance Library for Watch") (part "RES_0201_10R"))
    )
    (comp (ref "R11")
      (value "10k")
      (footprint "RESISTOR_SMD_0402")
      (description "RES SMD 3.3K OHM 1% 1/10W 0402")
      (fields
        (field (name "MANUFACTURER") "Panasonic Electronic Components")
        (field (name "MANUFACTURER PART NUMBER") "ERJ-2RKF3301X")
      )
      (libsource (lib "Maxium Referance Library for Watch") (part "RES_0402_3K3"))
    )
    (comp (ref "R12")
      (value "0R")
      (footprint "RESISTOR_SMD_0201")
      (description "RES SMD 10 OHM 1% 1/20W 0201")
      (fields
        (field (name "MANUFACTURER") "Panasonic Electronic Components")
        (field (name "MANUFACTURER PART NUMBER") "ERJ-1GEF10R0C")
      )
      (libsource (lib "Maxium Referance Library for Watch") (part "RES_0201_10R"))
    )
    (comp (ref "R13")
      (value "0R")
      (footprint "RESISTOR_SMD_0201")
      (description "RES SMD 10 OHM 1% 1/20W 0201")
      (fields
        (field (name "MANUFACTURER") "Panasonic Electronic Components")
        (field (name "MANUFACTURER PART NUMBER") "ERJ-1GEF10R0C")
      )
      (libsource (lib "Maxium Referance Library for Watch") (part "RES_0201_10R"))
    )
    (comp (ref "R14")
      (value "0R")
      (footprint "RESISTOR_SMD_0201")
      (description "RES SMD 10 OHM 1% 1/20W 0201")
      (fields
        (field (name "MANUFACTURER") "Panasonic Electronic Components")
        (field (name "MANUFACTURER PART NUMBER") "ERJ-1GEF10R0C")
      )
      (libsource (lib "Maxium Referance Library for Watch") (part "RES_0201_10R"))
    )
    (comp (ref "R15")
      (value "10k")
      (footprint "RESISTOR_SMD_0402")
      (description "RES SMD 3.3K OHM 1% 1/10W 0402")
      (fields
        (field (name "MANUFACTURER") "Panasonic Electronic Components")
        (field (name "MANUFACTURER PART NUMBER") "ERJ-2RKF3301X")
      )
      (libsource (lib "Maxium Referance Library for Watch") (part "RES_0402_3K3"))
    )
    (comp (ref "R16")
      (value "10k")
      (footprint "RESISTOR_SMD_0402")
      (description "RES SMD 3.3K OHM 1% 1/10W 0402")
      (fields
        (field (name "MANUFACTURER") "Panasonic Electronic Components")
        (field (name "MANUFACTURER PART NUMBER") "ERJ-2RKF3301X")
      )
      (libsource (lib "Maxium Referance Library for Watch") (part "RES_0402_3K3"))
    )
    (comp (ref "R17")
      (value "100k")
      (footprint "RESISTOR_SMD_0402")
      (description "RES SMD 3.3K OHM 1% 1/10W 0402")
      (fields
        (field (name "MANUFACTURER") "Panasonic Electronic Components")
        (field (name "MANUFACTURER PART NUMBER") "ERJ-2RKF3301X")
      )
      (libsource (lib "Maxium Referance Library for Watch") (part "RES_0402_3K3"))
    )
    (comp (ref "R18")
      (value "10k")
      (footprint "RESISTOR_SMD_0402")
      (description "RES SMD 3.3K OHM 1% 1/10W 0402")
      (fields
        (field (name "MANUFACTURER") "Panasonic Electronic Components")
        (field (name "MANUFACTURER PART NUMBER") "ERJ-2RKF3301X")
      )
      (libsource (lib "Maxium Referance Library for Watch") (part "RES_0402_3K3"))
    )
    (comp (ref "R19")
      (value "1K5")
      (footprint "RESISTOR_SMD_0402")
      (description "RES SMD 3.3K OHM 1% 1/10W 0402")
      (fields
        (field (name "MANUFACTURER") "Panasonic Electronic Components")
        (field (name "MANUFACTURER PART NUMBER") "ERJ-2RKF3301X")
      )
      (libsource (lib "Maxium Referance Library for Watch") (part "RES_0402_3K3"))
    )
    (comp (ref "R20")
      (value "4K7")
      (footprint "RESISTOR_SMD_0402")
      (description "RES SMD 3.3K OHM 1% 1/10W 0402")
      (fields
        (field (name "MANUFACTURER") "Panasonic Electronic Components")
        (field (name "MANUFACTURER PART NUMBER") "ERJ-2RKF3301X")
      )
      (libsource (lib "Maxium Referance Library for Watch") (part "RES_0402_3K3"))
    )
    (comp (ref "R21")
      (value "4K7")
      (footprint "RESISTOR_SMD_0402")
      (description "RES SMD 3.3K OHM 1% 1/10W 0402")
      (fields
        (field (name "MANUFACTURER") "Panasonic Electronic Components")
        (field (name "MANUFACTURER PART NUMBER") "ERJ-2RKF3301X")
      )
      (libsource (lib "Maxium Referance Library for Watch") (part "RES_0402_3K3"))
    )
    (comp (ref "R22")
      (value "1K5")
      (footprint "RESISTOR_SMD_0402")
      (description "RES SMD 3.3K OHM 1% 1/10W 0402")
      (fields
        (field (name "MANUFACTURER") "Panasonic Electronic Components")
        (field (name "MANUFACTURER PART NUMBER") "ERJ-2RKF3301X")
      )
      (libsource (lib "Maxium Referance Library for Watch") (part "RES_0402_3K3"))
    )
    (comp (ref "R23")
      (value "10k")
      (footprint "RESISTOR_SMD_0402")
      (description "RES SMD 3.3K OHM 1% 1/10W 0402")
      (fields
        (field (name "MANUFACTURER") "Panasonic Electronic Components")
        (field (name "MANUFACTURER PART NUMBER") "ERJ-2RKF3301X")
      )
      (libsource (lib "Maxium Referance Library for Watch") (part "RES_0402_3K3"))
    )
    (comp (ref "R24")
      (value "100")
      (footprint "RESISTOR_SMD_0402")
      (description "RES SMD 3.3K OHM 1% 1/10W 0402")
      (fields
        (field (name "MANUFACTURER") "Panasonic Electronic Components")
        (field (name "MANUFACTURER PART NUMBER") "ERJ-2RKF3301X")
      )
      (libsource (lib "Maxium Referance Library for Watch") (part "RES_0402_3K3"))
    )
    (comp (ref "R25")
      (value "100")
      (footprint "RESISTOR_SMD_0402")
      (description "RES SMD 3.3K OHM 1% 1/10W 0402")
      (fields
        (field (name "MANUFACTURER") "Panasonic Electronic Components")
        (field (name "MANUFACTURER PART NUMBER") "ERJ-2RKF3301X")
      )
      (libsource (lib "Maxium Referance Library for Watch") (part "RES_0402_3K3"))
    )
    (comp (ref "R26")
      (value "10k")
      (footprint "RESISTOR_SMD_0402")
      (description "RES SMD 3.3K OHM 1% 1/10W 0402")
      (fields
        (field (name "MANUFACTURER") "Panasonic Electronic Components")
        (field (name "MANUFACTURER PART NUMBER") "ERJ-2RKF3301X")
      )
      (libsource (lib "Maxium Referance Library for Watch") (part "RES_0402_3K3"))
    )
    (comp (ref "R27")
      (value "1M")
      (footprint "RESISTOR_SMD_0402")
      (description "RES SMD 3.3K OHM 1% 1/10W 0402")
      (fields
        (field (name "MANUFACTURER") "Panasonic Electronic Components")
        (field (name "MANUFACTURER PART NUMBER") "ERJ-2RKF3301X")
      )
      (libsource (lib "Maxium Referance Library for Watch") (part "RES_0402_3K3"))
    )
    (comp (ref "R28")
      (value "7K68")
      (footprint "RESISTOR_SMD_0402")
      (description "RES SMD 3.3K OHM 1% 1/10W 0402")
      (fields
        (field (name "MANUFACTURER") "Panasonic Electronic Components")
        (field (name "MANUFACTURER PART NUMBER") "ERJ-2RKF3301X")
      )
      (libsource (lib "Maxium Referance Library for Watch") (part "RES_0402_3K3"))
    )
    (comp (ref "R29")
      (value "4K7")
      (footprint "RESISTOR_SMD_0402")
      (description "RES SMD 3.3K OHM 1% 1/10W 0402")
      (fields
        (field (name "MANUFACTURER") "Panasonic Electronic Components")
        (field (name "MANUFACTURER PART NUMBER") "ERJ-2RKF3301X")
      )
      (libsource (lib "Maxium Referance Library for Watch") (part "RES_0402_3K3"))
    )
    (comp (ref "R30")
      (value "4K7")
      (footprint "RESISTOR_SMD_0402")
      (description "RES SMD 3.3K OHM 1% 1/10W 0402")
      (fields
        (field (name "MANUFACTURER") "Panasonic Electronic Components")
        (field (name "MANUFACTURER PART NUMBER") "ERJ-2RKF3301X")
      )
      (libsource (lib "Maxium Referance Library for Watch") (part "RES_0402_3K3"))
    )
    (comp (ref "R31")
      (value "0R")
      (footprint "RESISTOR_SMD_0201")
      (description "RES SMD 10 OHM 1% 1/20W 0201")
      (fields
        (field (name "MANUFACTURER") "Panasonic Electronic Components")
        (field (name "MANUFACTURER PART NUMBER") "ERJ-1GEF10R0C")
      )
      (libsource (lib "Maxium Referance Library for Watch") (part "RES_0201_10R"))
    )
    (comp (ref "R32")
      (value "100K")
      (footprint "RESISTOR_SMD_0402")
      (description "RES SMD 3.3K OHM 1% 1/10W 0402")
      (fields
        (field (name "MANUFACTURER") "Panasonic Electronic Components")
        (field (name "MANUFACTURER PART NUMBER") "ERJ-2RKF3301X")
      )
      (libsource (lib "Maxium Referance Library for Watch") (part "RES_0402_3K3"))
    )
    (comp (ref "R33")
      (value "100K")
      (footprint "RESISTOR_SMD_0402")
      (description "RES SMD 3.3K OHM 1% 1/10W 0402")
      (fields
        (field (name "MANUFACTURER") "Panasonic Electronic Components")
        (field (name "MANUFACTURER PART NUMBER") "ERJ-2RKF3301X")
      )
      (libsource (lib "Maxium Referance Library for Watch") (part "RES_0402_3K3"))
    )
    (comp (ref "R34")
      (value "100k")
      (footprint "RESISTOR_SMD_0402")
      (description "RES SMD 3.3K OHM 1% 1/10W 0402")
      (fields
        (field (name "MANUFACTURER") "Panasonic Electronic Components")
        (field (name "MANUFACTURER PART NUMBER") "ERJ-2RKF3301X")
      )
      (libsource (lib "Maxium Referance Library for Watch") (part "RES_0402_3K3"))
    )
    (comp (ref "R35")
      (value "470")
      (footprint "RESISTOR_SMD_0402")
      (description "RES SMD 3.3K OHM 1% 1/10W 0402")
      (fields
        (field (name "MANUFACTURER") "Panasonic Electronic Components")
        (field (name "MANUFACTURER PART NUMBER") "ERJ-2RKF3301X")
      )
      (libsource (lib "Maxium Referance Library for Watch") (part "RES_0402_3K3"))
    )
    (comp (ref "R36")
      (value "10k")
      (footprint "RESISTOR_SMD_0402")
      (description "RES SMD 3.3K OHM 1% 1/10W 0402")
      (fields
        (field (name "MANUFACTURER") "Panasonic Electronic Components")
        (field (name "MANUFACTURER PART NUMBER") "ERJ-2RKF3301X")
      )
      (libsource (lib "Maxium Referance Library for Watch") (part "RES_0402_3K3"))
    )
    (comp (ref "R37")
      (value "470")
      (footprint "RESISTOR_SMD_0402")
      (description "RES SMD 3.3K OHM 1% 1/10W 0402")
      (fields
        (field (name "MANUFACTURER") "Panasonic Electronic Components")
        (field (name "MANUFACTURER PART NUMBER") "ERJ-2RKF3301X")
      )
      (libsource (lib "Maxium Referance Library for Watch") (part "RES_0402_3K3"))
    )
    (comp (ref "R38")
      (value "10k")
      (footprint "RESISTOR_SMD_0402")
      (description "RES SMD 3.3K OHM 1% 1/10W 0402")
      (fields
        (field (name "MANUFACTURER") "Panasonic Electronic Components")
        (field (name "MANUFACTURER PART NUMBER") "ERJ-2RKF3301X")
      )
      (libsource (lib "Maxium Referance Library for Watch") (part "RES_0402_3K3"))
    )
    (comp (ref "R39")
      (value "5R1")
      (footprint "RESISTOR_SMD_0402")
      (description "RES SMD 49.9K OHM 1% 1/10W 0402")
      (fields
        (field (name "MANUFACTURER") "Panasonic Electronic Components")
        (field (name "MANUFACTURER PART NUMBER") "ERJ-2RKF4993X")
      )
      (libsource (lib "Maxium Referance Library for Watch") (part "RES_0402_499K"))
    )
    (comp (ref "R40")
      (value "5R1")
      (footprint "RESISTOR_SMD_0402")
      (description "RES SMD 49.9K OHM 1% 1/10W 0402")
      (fields
        (field (name "MANUFACTURER") "Panasonic Electronic Components")
        (field (name "MANUFACTURER PART NUMBER") "ERJ-2RKF4993X")
      )
      (libsource (lib "Maxium Referance Library for Watch") (part "RES_0402_499K"))
    )
    (comp (ref "R41")
      (value "100k")
      (footprint "RESISTOR_SMD_0402")
      (description "RES SMD 3.3K OHM 1% 1/10W 0402")
      (fields
        (field (name "MANUFACTURER") "Panasonic Electronic Components")
        (field (name "MANUFACTURER PART NUMBER") "ERJ-2RKF3301X")
      )
      (libsource (lib "Maxium Referance Library for Watch") (part "RES_0402_3K3"))
    )
    (comp (ref "U1")
      (value "HD3SS460")
      (footprint "WQFN28-0.8mm")
      (description "4 x 6 Channels USB Type-C Alternate Mode MUX")
      (libsource (lib "HD3SS460") (part "HDS3SS460"))
    )
    (comp (ref "U2")
      (value "STM32F103CBT7")
      (footprint "LQFP48-7mm*7mm")
      (description "32bit MCU")
      (libsource (lib "MySchLib") (part "STM32F303CBT7"))
    )
    (comp (ref "U3")
      (value "AZ1117EH-3.3")
      (footprint "SOT223_N")
      (description "3.3V Voltage Regulator")
      (libsource (lib "MySchLib") (part "AMS1117-3.3V"))
    )
    (comp (ref "U4")
      (value "LT7911D")
      (footprint "QFN64-7.5mm*7.5mm")
      (description "USB/MIPI port converter")
      (libsource (lib "MySchLib") (part "LT7911D"))
    )
    (comp (ref "U5")
      (value "ST1S12G12R")
      (footprint "SOT23 - 5")
      (description "voltage regulater")
      (fields (field (name "PUBLISHER") "Altium Limited"))
      (libsource (lib "MySchLib") (part "TD6810"))
    )
    (comp (ref "U6")
      (value "NCP114ASN180T1G")
      (footprint "SOT23 - 5")
      (description "1.8V LDO Voltage Regulator")
      (libsource (lib "MySchLib") (part "NCP718BSN180T1G"))
    )
    (comp (ref "U7")
      (value "LP3102QVF")
      (footprint "TDFN-10")
      (description "Dual channel charge pump power solution For TFT LCD Panel")
      (fields (field (name "PUBLISHER") "Altium Limited"))
      (libsource (lib "MySchLib") (part "LP3102QVP"))
    )
    (comp (ref "U8")
      (value "CS4344")
      (footprint "10LD TSSOP(3mm BODY)")
      (description "Stereo D/A Converter")
      (fields (field (name "PUBLISHER") "Altium Limited"))
      (libsource (lib "MySchLib") (part "CS4344"))
    )
    (comp (ref "U9")
      (value "LP3384")
      (footprint "SOT95P279X130-6N")
      (libsource (lib "SVN-840 Dev Board") (part "SOT23"))
    )
    (comp (ref "U10")
      (value "TXS0104EPWR")
      (footprint "PW14")
      (description "Voltage Level Translator Bidirectional 1 Circuit 4 Channel 24Mbps 14-TSSOP")
      (libsource (lib "SVN-840 Dev Board") (part "TXS0104E"))
    )
    (comp (ref "Y1")
      (value "8MHz")
      (footprint "Resonator_mini")
      (description "Crystal Oscillator")
      (fields (field (name "PUBLISHER") "Altium Limited"))
      (libsource (lib "MySchLib") (part "XTAL"))
    )
    (comp (ref "Y2")
      (value "27MHz")
      (footprint "Crystal resonator")
      (description "Crystal Oscillator")
      (fields (field (name "PUBLISHER") "Altium Limited"))
      (libsource (lib "MySchLib") (part "XTAL_2"))
    )
  )
  (nets
    (net (code "1") (name "+5V") (class "Default")
      (node (ref "C14") (pin "1") (pintype "passive"))
      (node (ref "C15") (pin "1") (pintype "passive"))
      (node (ref "C22") (pin "1") (pintype "passive"))
      (node (ref "C23") (pin "1") (pintype "passive"))
      (node (ref "C24") (pin "1") (pintype "passive"))
      (node (ref "C25") (pin "1") (pintype "passive"))
      (node (ref "C26") (pin "1") (pintype "passive"))
      (node (ref "C81") (pin "1") (pintype "passive"))
      (node (ref "C82") (pin "1") (pintype "passive"))
      (node (ref "D1") (pin "1") (pinfunction "K_1") (pintype "passive"))
      (node (ref "D2") (pin "1") (pinfunction "K_1") (pintype "passive"))
      (node (ref "L2") (pin "1") (pinfunction "1_1") (pintype "passive"))
      (node (ref "R22") (pin "2") (pintype "passive"))
      (node (ref "U3") (pin "3") (pinfunction "IN_3") (pintype "passive"))
      (node (ref "U5") (pin "4") (pinfunction "VIN_4") (pintype "passive"))
      (node (ref "U9") (pin "6") (pinfunction "VIN_6") (pintype "passive"))
    )
    (net (code "2") (name "/AMSEL") (class "Default")
      (node (ref "R16") (pin "1") (pintype "passive"))
      (node (ref "U1") (pin "8") (pinfunction "AMSEL_8") (pintype "passive"))
      (node (ref "U2") (pin "25") (pinfunction "PB12_25") (pintype "power_in"))
    )
    (net (code "3") (name "/AUDIO_L_O") (class "Default")
      (node (ref "C78") (pin "1") (pintype "passive"))
      (node (ref "J6") (pin "4") (pintype "passive"))
      (node (ref "R37") (pin "2") (pintype "passive"))
    )
    (net (code "4") (name "/AUDIO_R_O") (class "Default")
      (node (ref "C72") (pin "1") (pintype "passive"))
      (node (ref "J6") (pin "3") (pintype "passive"))
      (node (ref "R35") (pin "2") (pintype "passive"))
    )
    (net (code "5") (name "/AUX+") (class "Default")
      (node (ref "U1") (pin "14") (pinfunction "SBU2_14") (pintype "passive"))
      (node (ref "U4") (pin "17") (pinfunction "AUXP_17") (pintype "bidirectional"))
    )
    (net (code "6") (name "/AUX-") (class "Default")
      (node (ref "U1") (pin "13") (pinfunction "SBU1_13") (pintype "passive"))
      (node (ref "U4") (pin "18") (pinfunction "AUXN_18") (pintype "bidirectional"))
    )
    (net (code "7") (name "/BTN") (class "Default")
      (node (ref "C12") (pin "1") (pintype "passive"))
      (node (ref "K2") (pin "1") (pinfunction "1_1") (pintype "passive"))
      (node (ref "R21") (pin "1") (pintype "passive"))
      (node (ref "U2") (pin "30") (pinfunction "PA9_30") (pintype "power_in"))
    )
    (net (code "8") (name "/CC1") (class "Default")
      (node (ref "R10") (pin "1") (pintype "passive"))
      (node (ref "U4") (pin "14") (pinfunction "UCC1_14") (pintype "power_in"))
    )
    (net (code "9") (name "/CC2") (class "Default")
      (node (ref "R12") (pin "2") (pintype "passive"))
      (node (ref "U4") (pin "15") (pinfunction "UCC2_15") (pintype "power_in"))
    )
    (net (code "10") (name "/COM_CLK") (class "Default")
      (node (ref "J2") (pin "3") (pinfunction "3_3") (pintype "passive"))
      (node (ref "R2") (pin "1") (pintype "passive"))
      (node (ref "R24") (pin "1") (pintype "passive"))
    )
    (net (code "11") (name "/COM_DIO") (class "Default")
      (node (ref "J2") (pin "4") (pinfunction "4_4") (pintype "passive"))
      (node (ref "R1") (pin "1") (pintype "passive"))
      (node (ref "R25") (pin "1") (pintype "passive"))
    )
    (net (code "12") (name "/CSCL") (class "Default")
      (node (ref "J5") (pin "1") (pinfunction "1_1") (pintype "passive"))
      (node (ref "R29") (pin "1") (pintype "passive"))
      (node (ref "R9") (pin "2") (pintype "passive"))
      (node (ref "U4") (pin "21") (pinfunction "CSCL_21") (pintype "input"))
    )
    (net (code "13") (name "/CSDA") (class "Default")
      (node (ref "J5") (pin "2") (pinfunction "2_2") (pintype "passive"))
      (node (ref "R30") (pin "1") (pintype "passive"))
      (node (ref "R8") (pin "2") (pintype "passive"))
      (node (ref "U4") (pin "22") (pinfunction "CSDA_22") (pintype "bidirectional"))
    )
    (net (code "14") (name "/D1_SSRX_N") (class "Default")
      (node (ref "J8") (pin "6") (pinfunction "StdA_SSRX+_6") (pintype "passive"))
      (node (ref "U1") (pin "27") (pinfunction "SSRX-_27") (pintype "passive"))
    )
    (net (code "15") (name "/D1_SSRX_P") (class "Default")
      (node (ref "J8") (pin "5") (pinfunction "StdA_SSRX-_5") (pintype "passive"))
      (node (ref "U1") (pin "28") (pinfunction "SSRX+_28") (pintype "passive"))
    )
    (net (code "16") (name "/D2_SSTX_N") (class "Default")
      (node (ref "J8") (pin "9") (pinfunction "StdA_SSTX+_9") (pintype "passive"))
      (node (ref "U1") (pin "25") (pinfunction "SSTX-_25") (pintype "passive"))
    )
    (net (code "17") (name "/D2_SSTX_P") (class "Default")
      (node (ref "J8") (pin "8") (pinfunction "StdA_SSTX-_8") (pintype "passive"))
      (node (ref "U1") (pin "26") (pinfunction "SSTX+_26") (pintype "passive"))
    )
    (net (code "18") (name "/DP_D0_N") (class "Default")
      (node (ref "U1") (pin "23") (pinfunction "LnD-_23") (pintype "passive"))
      (node (ref "U4") (pin "3") (pinfunction "D0N_3") (pintype "input"))
    )
    (net (code "19") (name "/DP_D0_P") (class "Default")
      (node (ref "U1") (pin "24") (pinfunction "LnD+_24") (pintype "passive"))
      (node (ref "U4") (pin "2") (pinfunction "D0P_2") (pintype "input"))
    )
    (net (code "20") (name "/DP_D1_N") (class "Default")
      (node (ref "U1") (pin "20") (pinfunction "LnC-_20") (pintype "passive"))
      (node (ref "U4") (pin "6") (pinfunction "D1N_6") (pintype "input"))
    )
    (net (code "21") (name "/DP_D1_P") (class "Default")
      (node (ref "U1") (pin "21") (pinfunction "LnC+_21") (pintype "passive"))
      (node (ref "U4") (pin "5") (pinfunction "D1P_5") (pintype "input"))
    )
    (net (code "22") (name "/DP_D2_N") (class "Default")
      (node (ref "U1") (pin "18") (pinfunction "LnB-_18") (pintype "passive"))
      (node (ref "U4") (pin "9") (pinfunction "D2N_9") (pintype "input"))
    )
    (net (code "23") (name "/DP_D2_P") (class "Default")
      (node (ref "U1") (pin "19") (pinfunction "LnB+_19") (pintype "passive"))
      (node (ref "U4") (pin "8") (pinfunction "D2P_8") (pintype "input"))
    )
    (net (code "24") (name "/DP_D3_N") (class "Default")
      (node (ref "U1") (pin "15") (pinfunction "LnA-_15") (pintype "passive"))
      (node (ref "U4") (pin "12") (pinfunction "D3N_12") (pintype "input"))
    )
    (net (code "25") (name "/DP_D3_P") (class "Default")
      (node (ref "U1") (pin "16") (pinfunction "LnA+_16") (pintype "passive"))
      (node (ref "U4") (pin "11") (pinfunction "D3P_11") (pintype "input"))
    )
    (net (code "26") (name "/Hsync") (class "Default")
      (node (ref "U10") (pin "13") (pinfunction "B1_13") (pintype "bidirectional"))
      (node (ref "U2") (pin "3") (pinfunction "PC14_3") (pintype "power_in"))
    )
    (net (code "27") (name "/Hsync_L") (class "Default")
      (node (ref "J7") (pin "5") (pinfunction "HSYNC_5") (pintype "output"))
      (node (ref "U10") (pin "2") (pinfunction "A1_2") (pintype "bidirectional"))
    )
    (net (code "28") (name "/IIS_D0") (class "Default")
      (node (ref "U4") (pin "32") (pinfunction "IIS_D0_32") (pintype "bidirectional"))
      (node (ref "U8") (pin "1") (pinfunction "SDIN_1") (pintype "input"))
    )
    (net (code "29") (name "/IIS_MCLK") (class "Default")
      (node (ref "U4") (pin "29") (pinfunction "IIS_MCLK_29") (pintype "bidirectional"))
      (node (ref "U8") (pin "4") (pinfunction "MCLK_4") (pintype "input"))
    )
    (net (code "30") (name "/IIS_SCLK") (class "Default")
      (node (ref "U4") (pin "28") (pinfunction "IIS_SCLK_28") (pintype "bidirectional"))
      (node (ref "U8") (pin "2") (pinfunction "DEM/SCLK_2") (pintype "input"))
    )
    (net (code "31") (name "/IIS_WS") (class "Default")
      (node (ref "U4") (pin "27") (pinfunction "IIS_WS_27") (pintype "bidirectional"))
      (node (ref "U8") (pin "3") (pinfunction "LRCK_3") (pintype "input"))
    )
    (net (code "32") (name "/INTA") (class "Default")
      (node (ref "J2") (pin "8") (pinfunction "8_8") (pintype "passive"))
      (node (ref "U2") (pin "2") (pinfunction "PC13/TAMP/RTC_2") (pintype "power_in"))
    )
    (net (code "33") (name "/LCD_ON") (class "Default")
      (node (ref "P1") (pin "1") (pinfunction "1_1") (pintype "passive"))
      (node (ref "R41") (pin "2") (pintype "passive"))
      (node (ref "U2") (pin "15") (pinfunction "PA5_15") (pintype "power_in"))
      (node (ref "U9") (pin "4") (pinfunction "SHDN_4") (pintype "passive"))
    )
    (net (code "34") (name "/LCD_VCCEN") (class "Default")
      (node (ref "U2") (pin "14") (pinfunction "PA4_14") (pintype "power_in"))
      (node (ref "U6") (pin "3") (pinfunction "EN_3") (pintype "passive"))
    )
    (net (code "35") (name "/LCD_VSEN") (class "Default")
      (node (ref "R34") (pin "2") (pintype "passive"))
      (node (ref "U2") (pin "13") (pinfunction "PA3_13") (pintype "power_in"))
      (node (ref "U7") (pin "5") (pinfunction "EN_5") (pintype "passive"))
    )
    (net (code "36") (name "/LED1_CON") (class "Default")
      (node (ref "R3") (pin "2") (pintype "passive"))
      (node (ref "U2") (pin "27") (pinfunction "PB14_27") (pintype "power_in"))
    )
    (net (code "37") (name "/LED2_CON") (class "Default")
      (node (ref "R4") (pin "2") (pintype "passive"))
      (node (ref "U2") (pin "28") (pinfunction "PB15_28") (pintype "power_in"))
    )
    (net (code "38") (name "/LED3_CON") (class "Default")
      (node (ref "R5") (pin "2") (pintype "passive"))
      (node (ref "U2") (pin "29") (pinfunction "PA8_29") (pintype "power_in"))
    )
    (net (code "39") (name "/LEDPWM") (class "Default")
      (node (ref "P1") (pin "2") (pinfunction "2_2") (pintype "passive"))
      (node (ref "U10") (pin "10") (pinfunction "B4_10") (pintype "bidirectional"))
      (node (ref "U2") (pin "12") (pinfunction "PA2_12") (pintype "power_in"))
    )
    (net (code "40") (name "/LEDPWM_L") (class "Default")
      (node (ref "J7") (pin "44") (pinfunction "LEDPWM_44") (pintype "output"))
      (node (ref "U10") (pin "5") (pinfunction "A4_5") (pintype "bidirectional"))
    )
    (net (code "41") (name "/MIPI_N0_CLK_N") (class "Default")
      (node (ref "J7") (pin "14") (pinfunction "DSI_A_CLK-_14") (pintype "input"))
      (node (ref "U4") (pin "54") (pinfunction "MCK_N1_54") (pintype "output"))
    )
    (net (code "42") (name "/MIPI_N0_CLK_P") (class "Default")
      (node (ref "J7") (pin "16") (pinfunction "DSI_A_CLK+_16") (pintype "input"))
      (node (ref "U4") (pin "53") (pinfunction "MCK_P1_53") (pintype "output"))
    )
    (net (code "43") (name "/MIPI_N0_D0_N") (class "Default")
      (node (ref "J7") (pin "9") (pinfunction "DSI_A_D0-_9") (pintype "bidirectional"))
      (node (ref "U4") (pin "56") (pinfunction "M2_N1_56") (pintype "output"))
    )
    (net (code "44") (name "/MIPI_N0_D0_P") (class "Default")
      (node (ref "J7") (pin "11") (pinfunction "DSI_A_D0+_11") (pintype "bidirectional"))
      (node (ref "U4") (pin "55") (pinfunction "M2_P1_55") (pintype "open_collector"))
    )
    (net (code "45") (name "/MIPI_N0_D1_N") (class "Default")
      (node (ref "J7") (pin "15") (pinfunction "DSI_A_D1-_15") (pintype "input"))
      (node (ref "U4") (pin "52") (pinfunction "M1_N1_52") (pintype "output"))
    )
    (net (code "46") (name "/MIPI_N0_D1_P") (class "Default")
      (node (ref "J7") (pin "17") (pinfunction "DSI_A_D1+_17") (pintype "input"))
      (node (ref "U4") (pin "51") (pinfunction "M1_P1_51") (pintype "output"))
    )
    (net (code "47") (name "/MIPI_N0_D2_N") (class "Default")
      (node (ref "J7") (pin "20") (pinfunction "DSI_A_D2-_20") (pintype "input"))
      (node (ref "U4") (pin "50") (pinfunction "M0_N1_50") (pintype "output"))
    )
    (net (code "48") (name "/MIPI_N0_D2_P") (class "Default")
      (node (ref "J7") (pin "22") (pinfunction "DSI_A_D2+_22") (pintype "input"))
      (node (ref "U4") (pin "49") (pinfunction "M0_P1_49") (pintype "output"))
    )
    (net (code "49") (name "/MIPI_N0_D3_N") (class "Default")
      (node (ref "J7") (pin "8") (pinfunction "DSI_A_D3-_8") (pintype "input"))
      (node (ref "U4") (pin "58") (pinfunction "M3_N1_58") (pintype "output"))
    )
    (net (code "50") (name "/MIPI_N0_D3_P") (class "Default")
      (node (ref "J7") (pin "10") (pinfunction "DSI_A_D3+_10") (pintype "input"))
      (node (ref "U4") (pin "57") (pinfunction "M3_P1_57") (pintype "output"))
    )
    (net (code "51") (name "/MIPI_N1_CLK_N") (class "Default")
      (node (ref "J7") (pin "29") (pinfunction "DSI_B_CLK-_29") (pintype "input"))
      (node (ref "U4") (pin "40") (pinfunction "MCK_N3_40") (pintype "output"))
    )
    (net (code "52") (name "/MIPI_N1_CLK_P") (class "Default")
      (node (ref "J7") (pin "27") (pinfunction "DSI_B_CLK+_27") (pintype "input"))
      (node (ref "U4") (pin "39") (pinfunction "MCK_P3_39") (pintype "output"))
    )
    (net (code "53") (name "/MIPI_N1_D0_N") (class "Default")
      (node (ref "J7") (pin "34") (pinfunction "DSI_B_D0-_34") (pintype "bidirectional"))
      (node (ref "U4") (pin "37") (pinfunction "M1_P3_37") (pintype "output"))
    )
    (net (code "54") (name "/MIPI_N1_D0_P") (class "Default")
      (node (ref "J7") (pin "32") (pinfunction "DSI_B_D0+_32") (pintype "bidirectional"))
      (node (ref "U4") (pin "38") (pinfunction "M1_N3_38") (pintype "output"))
    )
    (net (code "55") (name "/MIPI_N1_D1_N") (class "Default")
      (node (ref "J7") (pin "28") (pinfunction "DSI_B_D1-_28") (pintype "input"))
      (node (ref "U4") (pin "41") (pinfunction "M2_P3_41") (pintype "output"))
    )
    (net (code "56") (name "/MIPI_N1_D1_P") (class "Default")
      (node (ref "J7") (pin "26") (pinfunction "DSI_B_D1+_26") (pintype "input"))
      (node (ref "U4") (pin "42") (pinfunction "M2_N3_42") (pintype "output"))
    )
    (net (code "57") (name "/MIPI_N1_D2_N") (class "Default")
      (node (ref "J7") (pin "23") (pinfunction "DSI_B_D2-_23") (pintype "input"))
      (node (ref "U4") (pin "43") (pinfunction "M3_P3_43") (pintype "output"))
    )
    (net (code "58") (name "/MIPI_N1_D2_P") (class "Default")
      (node (ref "J7") (pin "21") (pinfunction "DSI_B_D2+_21") (pintype "input"))
      (node (ref "U4") (pin "44") (pinfunction "M3_N3_44") (pintype "output"))
    )
    (net (code "59") (name "/MIPI_N1_D3_N") (class "Default")
      (node (ref "J7") (pin "35") (pinfunction "DSI_B_D3-_35") (pintype "input"))
      (node (ref "U4") (pin "35") (pinfunction "M0_P3_35") (pintype "output"))
    )
    (net (code "60") (name "/MIPI_N1_D3_P") (class "Default")
      (node (ref "J7") (pin "33") (pinfunction "DSI_B_D3+_33") (pintype "input"))
      (node (ref "U4") (pin "36") (pinfunction "M0_N3_36") (pintype "output"))
    )
    (net (code "61") (name "/NRST") (class "Default")
      (node (ref "C11") (pin "1") (pintype "passive"))
      (node (ref "K1") (pin "1") (pinfunction "1_1") (pintype "passive"))
      (node (ref "R20") (pin "1") (pintype "passive"))
      (node (ref "U2") (pin "7") (pinfunction "NRST_7") (pintype "power_in"))
    )
    (net (code "62") (name "/POL") (class "Default")
      (node (ref "R18") (pin "1") (pintype "passive"))
      (node (ref "U1") (pin "3") (pinfunction "POL_3") (pintype "passive"))
      (node (ref "U2") (pin "17") (pinfunction "PA7_17") (pintype "power_in"))
      (node (ref "U4") (pin "26") (pinfunction "GPIO5_26") (pintype "bidirectional"))
    )
    (net (code "63") (name "/RESX") (class "Default")
      (node (ref "U10") (pin "12") (pinfunction "B2_12") (pintype "bidirectional"))
      (node (ref "U2") (pin "10") (pinfunction "PA0/WKUP_10") (pintype "power_in"))
    )
    (net (code "64") (name "/RESX_L") (class "Default")
      (node (ref "J7") (pin "38") (pinfunction "RESX_38") (pintype "input"))
      (node (ref "U10") (pin "3") (pinfunction "A2_3") (pintype "bidirectional"))
    )
    (net (code "65") (name "/REXT") (class "Default")
      (node (ref "R28") (pin "2") (pintype "passive"))
      (node (ref "U4") (pin "61") (pinfunction "REXT_61") (pintype "output"))
    )
    (net (code "66") (name "/RRX1_N") (class "Default")
      (node (ref "J1") (pin "B10") (pinfunction "RX1-_B10") (pintype "passive"))
      (node (ref "R7") (pin "1") (pintype "passive"))
    )
    (net (code "67") (name "/RRX1_P") (class "Default")
      (node (ref "J1") (pin "B11") (pinfunction "RX1+_B11") (pintype "passive"))
      (node (ref "R6") (pin "1") (pintype "passive"))
    )
    (net (code "68") (name "/RRX2_N") (class "Default")
      (node (ref "J1") (pin "A10") (pinfunction "RX2-_A10") (pintype "passive"))
      (node (ref "R13") (pin "1") (pintype "passive"))
    )
    (net (code "69") (name "/RRX2_P") (class "Default")
      (node (ref "J1") (pin "A11") (pinfunction "RX2+_A11") (pintype "passive"))
      (node (ref "R14") (pin "1") (pintype "passive"))
    )
    (net (code "70") (name "/RSTN") (class "Default")
      (node (ref "C19") (pin "1") (pintype "passive"))
      (node (ref "R26") (pin "1") (pintype "passive"))
      (node (ref "U2") (pin "19") (pinfunction "PB1_19") (pintype "power_in"))
      (node (ref "U4") (pin "20") (pinfunction "RST_N_20") (pintype "input"))
    )
    (net (code "71") (name "/RX1_N") (class "Default")
      (node (ref "R7") (pin "2") (pintype "passive"))
      (node (ref "U1") (pin "2") (pinfunction "CRX1-_2") (pintype "passive"))
    )
    (net (code "72") (name "/RX1_P") (class "Default")
      (node (ref "R6") (pin "2") (pintype "passive"))
      (node (ref "U1") (pin "1") (pinfunction "CRX1+_1") (pintype "passive"))
    )
    (net (code "73") (name "/RX2_N") (class "Default")
      (node (ref "R13") (pin "2") (pintype "passive"))
      (node (ref "U1") (pin "9") (pinfunction "CRX2+_9") (pintype "passive"))
    )
    (net (code "74") (name "/RX2_P") (class "Default")
      (node (ref "R14") (pin "2") (pintype "passive"))
      (node (ref "U1") (pin "10") (pinfunction "CRX2-_10") (pintype "passive"))
    )
    (net (code "75") (name "/SBU1") (class "Default")
      (node (ref "C5") (pin "2") (pintype "passive"))
      (node (ref "U1") (pin "11") (pinfunction "CSBU1_11") (pintype "passive"))
    )
    (net (code "76") (name "/SBU2") (class "Default")
      (node (ref "C4") (pin "1") (pintype "passive"))
      (node (ref "U1") (pin "12") (pinfunction "CSBU2_12") (pintype "passive"))
    )
    (net (code "77") (name "/SDWIO") (class "Default")
      (node (ref "J3") (pin "3") (pinfunction "3_3") (pintype "passive"))
      (node (ref "U2") (pin "34") (pinfunction "PA13_34") (pintype "power_in"))
    )
    (net (code "78") (name "/SLEEP_33") (class "Default")
      (node (ref "U2") (pin "20") (pinfunction "PB2_20") (pintype "power_in"))
      (node (ref "U4") (pin "19") (pinfunction "SLEEP_33_19") (pintype "input"))
    )
    (net (code "79") (name "/SWCLK") (class "Default")
      (node (ref "J3") (pin "2") (pinfunction "2_2") (pintype "passive"))
      (node (ref "U2") (pin "37") (pinfunction "PA14_37") (pintype "power_in"))
    )
    (net (code "80") (name "/TE") (class "Default")
      (node (ref "U10") (pin "11") (pinfunction "B3_11") (pintype "bidirectional"))
      (node (ref "U2") (pin "11") (pinfunction "PA1_11") (pintype "power_in"))
    )
    (net (code "81") (name "/TE_L") (class "Default")
      (node (ref "J7") (pin "40") (pinfunction "TE_40") (pintype "output"))
      (node (ref "U10") (pin "4") (pinfunction "A3_4") (pintype "bidirectional"))
    )
    (net (code "82") (name "/TTX1_N") (class "Default")
      (node (ref "C3") (pin "1") (pintype "passive"))
      (node (ref "J1") (pin "A3") (pinfunction "TX1-_A3") (pintype "passive"))
    )
    (net (code "83") (name "/TTX1_P") (class "Default")
      (node (ref "C2") (pin "1") (pintype "passive"))
      (node (ref "J1") (pin "A2") (pinfunction "TX1+_A2") (pintype "passive"))
    )
    (net (code "84") (name "/TTX2_N") (class "Default")
      (node (ref "C6") (pin "2") (pintype "passive"))
      (node (ref "J1") (pin "B3") (pinfunction "TX2-_B3") (pintype "passive"))
    )
    (net (code "85") (name "/TTX2_P") (class "Default")
      (node (ref "C7") (pin "2") (pintype "passive"))
      (node (ref "J1") (pin "B2") (pinfunction "TX2+_B2") (pintype "passive"))
    )
    (net (code "86") (name "/TX1_N") (class "Default")
      (node (ref "C3") (pin "2") (pintype "passive"))
      (node (ref "U1") (pin "5") (pinfunction "CTX1-_5") (pintype "passive"))
    )
    (net (code "87") (name "/TX1_P") (class "Default")
      (node (ref "C2") (pin "2") (pintype "passive"))
      (node (ref "U1") (pin "4") (pinfunction "CTX1+_4") (pintype "passive"))
    )
    (net (code "88") (name "/TX2_N") (class "Default")
      (node (ref "C6") (pin "1") (pintype "passive"))
      (node (ref "U1") (pin "6") (pinfunction "CTX2+_6") (pintype "passive"))
    )
    (net (code "89") (name "/TX2_P") (class "Default")
      (node (ref "C7") (pin "1") (pintype "passive"))
      (node (ref "U1") (pin "7") (pinfunction "CTX2-_7") (pintype "passive"))
    )
    (net (code "90") (name "/USB_D_N") (class "Default")
      (node (ref "J1") (pin "A7") (pinfunction "D-1_A7") (pintype "passive"))
      (node (ref "J1") (pin "B7") (pinfunction "D-2_B7") (pintype "passive"))
      (node (ref "U2") (pin "32") (pinfunction "PA11_32") (pintype "power_in"))
    )
    (net (code "91") (name "/USB_D_P") (class "Default")
      (node (ref "J1") (pin "A6") (pinfunction "D+1_A6") (pintype "passive"))
      (node (ref "J1") (pin "B6") (pinfunction "D+2_B6") (pintype "passive"))
      (node (ref "R19") (pin "1") (pintype "passive"))
      (node (ref "U2") (pin "33") (pinfunction "PA12_33") (pintype "power_in"))
    )
    (net (code "92") (name "/Vsync") (class "Default")
      (node (ref "U2") (pin "16") (pinfunction "PA6_16") (pintype "power_in"))
      (node (ref "U4") (pin "31") (pinfunction "Vsync_OOT/SPDIF_31") (pintype "bidirectional"))
    )
    (net (code "93") (name "/XTALI") (class "Default")
      (node (ref "C21") (pin "1") (pintype "passive"))
      (node (ref "R27") (pin "1") (pintype "passive"))
      (node (ref "U4") (pin "64") (pinfunction "XTALI_64") (pintype "bidirectional"))
      (node (ref "Y2") (pin "3") (pinfunction "OSC2_3") (pintype "passive"))
    )
    (net (code "94") (name "/XTALO") (class "Default")
      (node (ref "C20") (pin "1") (pintype "passive"))
      (node (ref "R27") (pin "2") (pintype "passive"))
      (node (ref "U4") (pin "63") (pinfunction "XTALO_63") (pintype "bidirectional"))
      (node (ref "Y2") (pin "1") (pinfunction "OSC1_1") (pintype "passive"))
    )
    (net (code "95") (name "GND") (class "Default")
      (node (ref "C1") (pin "1") (pintype "passive"))
      (node (ref "C10") (pin "1") (pintype "passive"))
      (node (ref "C11") (pin "2") (pintype "passive"))
      (node (ref "C12") (pin "2") (pintype "passive"))
      (node (ref "C13") (pin "1") (pintype "passive"))
      (node (ref "C14") (pin "2") (pintype "passive"))
      (node (ref "C15") (pin "2") (pintype "passive"))
      (node (ref "C16") (pin "2") (pintype "passive"))
      (node (ref "C17") (pin "2") (pintype "passive"))
      (node (ref "C18") (pin "2") (pintype "passive"))
      (node (ref "C19") (pin "2") (pintype "passive"))
      (node (ref "C20") (pin "2") (pintype "passive"))
      (node (ref "C21") (pin "2") (pintype "passive"))
      (node (ref "C22") (pin "2") (pintype "passive"))
      (node (ref "C23") (pin "2") (pintype "passive"))
      (node (ref "C24") (pin "2") (pintype "passive"))
      (node (ref "C25") (pin "2") (pintype "passive"))
      (node (ref "C26") (pin "2") (pintype "passive"))
      (node (ref "C27") (pin "2") (pintype "passive"))
      (node (ref "C28") (pin "2") (pintype "passive"))
      (node (ref "C30") (pin "2") (pintype "passive"))
      (node (ref "C31") (pin "2") (pintype "passive"))
      (node (ref "C32") (pin "2") (pintype "passive"))
      (node (ref "C33") (pin "2") (pintype "passive"))
      (node (ref "C34") (pin "2") (pintype "passive"))
      (node (ref "C35") (pin "2") (pintype "passive"))
      (node (ref "C36") (pin "2") (pintype "passive"))
      (node (ref "C37") (pin "2") (pintype "passive"))
      (node (ref "C38") (pin "2") (pintype "passive"))
      (node (ref "C39") (pin "2") (pintype "passive"))
      (node (ref "C40") (pin "2") (pintype "passive"))
      (node (ref "C41") (pin "2") (pintype "passive"))
      (node (ref "C42") (pin "2") (pintype "passive"))
      (node (ref "C43") (pin "2") (pintype "passive"))
      (node (ref "C44") (pin "2") (pintype "passive"))
      (node (ref "C45") (pin "2") (pintype "passive"))
      (node (ref "C46") (pin "2") (pintype "passive"))
      (node (ref "C47") (pin "2") (pintype "passive"))
      (node (ref "C48") (pin "2") (pintype "passive"))
      (node (ref "C49") (pin "2") (pintype "passive"))
      (node (ref "C50") (pin "2") (pintype "passive"))
      (node (ref "C51") (pin "2") (pintype "passive"))
      (node (ref "C52") (pin "2") (pintype "passive"))
      (node (ref "C53") (pin "2") (pintype "passive"))
      (node (ref "C54") (pin "2") (pintype "passive"))
      (node (ref "C55") (pin "2") (pintype "passive"))
      (node (ref "C56") (pin "2") (pintype "passive"))
      (node (ref "C57") (pin "2") (pintype "passive"))
      (node (ref "C58") (pin "2") (pintype "passive"))
      (node (ref "C59") (pin "2") (pintype "passive"))
      (node (ref "C60") (pin "2") (pintype "passive"))
      (node (ref "C63") (pin "2") (pintype "passive"))
      (node (ref "C64") (pin "2") (pintype "passive"))
      (node (ref "C65") (pin "2") (pintype "passive"))
      (node (ref "C66") (pin "2") (pintype "passive"))
      (node (ref "C68") (pin "2") (pintype "passive"))
      (node (ref "C69") (pin "2") (pintype "passive"))
      (node (ref "C70") (pin "2") (pintype "passive"))
      (node (ref "C71") (pin "2") (pintype "passive"))
      (node (ref "C72") (pin "2") (pintype "passive"))
      (node (ref "C75") (pin "2") (pintype "passive"))
      (node (ref "C76") (pin "2") (pintype "passive"))
      (node (ref "C77") (pin "2") (pintype "passive"))
      (node (ref "C78") (pin "2") (pintype "passive"))
      (node (ref "C79") (pin "2") (pintype "passive"))
      (node (ref "C8") (pin "2") (pintype "passive"))
      (node (ref "C80") (pin "2") (pintype "passive"))
      (node (ref "C81") (pin "2") (pintype "passive"))
      (node (ref "C82") (pin "2") (pintype "passive"))
      (node (ref "C83") (pin "2") (pintype "passive"))
      (node (ref "C84") (pin "2") (pintype "passive"))
      (node (ref "C85") (pin "2") (pintype "passive"))
      (node (ref "C9") (pin "2") (pintype "passive"))
      (node (ref "D2") (pin "2") (pinfunction "A_2") (pintype "passive"))
      (node (ref "J1") (pin "1") (pinfunction "GND_1") (pintype "passive"))
      (node (ref "J1") (pin "2") (pinfunction "GND_2") (pintype "passive"))
      (node (ref "J1") (pin "3") (pinfunction "GND_3") (pintype "passive"))
      (node (ref "J1") (pin "4") (pinfunction "GND_4") (pintype "passive"))
      (node (ref "J1") (pin "A1") (pinfunction "GND_A1") (pintype "passive"))
      (node (ref "J1") (pin "A12") (pinfunction "GND_A12") (pintype "passive"))
      (node (ref "J1") (pin "B1") (pinfunction "GND_B1") (pintype "passive"))
      (node (ref "J1") (pin "B12") (pinfunction "GND_B12") (pintype "passive"))
      (node (ref "J2") (pin "2") (pinfunction "2_2") (pintype "passive"))
      (node (ref "J2") (pin "7") (pinfunction "7_7") (pintype "passive"))
      (node (ref "J3") (pin "4") (pinfunction "4_4") (pintype "passive"))
      (node (ref "J5") (pin "3") (pinfunction "3_3") (pintype "passive"))
      (node (ref "J6") (pin "2") (pintype "passive"))
      (node (ref "J7") (pin "1") (pinfunction "GND_1") (pintype "passive"))
      (node (ref "J7") (pin "12") (pinfunction "GND_12") (pintype "passive"))
      (node (ref "J7") (pin "13") (pinfunction "GND_13") (pintype "passive"))
      (node (ref "J7") (pin "18") (pinfunction "GND_18") (pintype "passive"))
      (node (ref "J7") (pin "19") (pinfunction "GND_19") (pintype "passive"))
      (node (ref "J7") (pin "2") (pinfunction "GND_2") (pintype "passive"))
      (node (ref "J7") (pin "24") (pinfunction "GND_24") (pintype "passive"))
      (node (ref "J7") (pin "25") (pinfunction "GND_25") (pintype "passive"))
      (node (ref "J7") (pin "30") (pinfunction "GND_30") (pintype "passive"))
      (node (ref "J7") (pin "31") (pinfunction "GND_31") (pintype "passive"))
      (node (ref "J7") (pin "36") (pinfunction "GND_36") (pintype "passive"))
      (node (ref "J7") (pin "37") (pinfunction "GND_37") (pintype "passive"))
      (node (ref "J7") (pin "42") (pinfunction "GND_42") (pintype "passive"))
      (node (ref "J7") (pin "43") (pinfunction "GND_43") (pintype "passive"))
      (node (ref "J7") (pin "6") (pinfunction "GND_6") (pintype "passive"))
      (node (ref "J7") (pin "7") (pinfunction "GND_7") (pintype "passive"))
      (node (ref "J8") (pin "10") (pinfunction "Sheild_10") (pintype "passive"))
      (node (ref "J8") (pin "4") (pinfunction "GND_4") (pintype "passive"))
      (node (ref "J8") (pin "7") (pinfunction "GND_DRAIN_7") (pintype "passive"))
      (node (ref "K1") (pin "2") (pinfunction "2_2") (pintype "passive"))
      (node (ref "K2") (pin "2") (pinfunction "2_2") (pintype "passive"))
      (node (ref "LED1") (pin "2") (pinfunction "K_2") (pintype "passive"))
      (node (ref "LED2") (pin "2") (pinfunction "K_2") (pintype "passive"))
      (node (ref "LED3") (pin "2") (pinfunction "K_2") (pintype "passive"))
      (node (ref "LED4") (pin "2") (pinfunction "K_2") (pintype "passive"))
      (node (ref "R16") (pin "2") (pintype "passive"))
      (node (ref "R17") (pin "1") (pintype "passive"))
      (node (ref "R23") (pin "1") (pintype "passive"))
      (node (ref "R28") (pin "1") (pintype "passive"))
      (node (ref "R33") (pin "1") (pintype "passive"))
      (node (ref "R34") (pin "1") (pintype "passive"))
      (node (ref "R36") (pin "1") (pintype "passive"))
      (node (ref "R38") (pin "1") (pintype "passive"))
      (node (ref "R39") (pin "1") (pintype "passive"))
      (node (ref "R40") (pin "1") (pintype "passive"))
      (node (ref "R41") (pin "1") (pintype "passive"))
      (node (ref "U1") (pin "PAD") (pinfunction "GND_PAD") (pintype "passive"))
      (node (ref "U10") (pin "7") (pinfunction "GND_7") (pintype "passive"))
      (node (ref "U2") (pin "23") (pinfunction "VSS1_23") (pintype "power_in"))
      (node (ref "U2") (pin "35") (pinfunction "VSS2_35") (pintype "power_in"))
      (node (ref "U2") (pin "47") (pinfunction "VSS_47") (pintype "power_in"))
      (node (ref "U2") (pin "8") (pinfunction "VSSA/VREF-_8") (pintype "power_in"))
      (node (ref "U3") (pin "1") (pinfunction "GND_1") (pintype "passive"))
      (node (ref "U4") (pin "65") (pinfunction "PAD_65") (pintype "power_in"))
      (node (ref "U5") (pin "2") (pinfunction "GND_2") (pintype "passive"))
      (node (ref "U6") (pin "2") (pinfunction "GND_2") (pintype "passive"))
      (node (ref "U7") (pin "11") (pinfunction "GND_11") (pintype "passive"))
      (node (ref "U8") (pin "8") (pinfunction "GND_8") (pintype "passive"))
      (node (ref "U9") (pin "2") (pinfunction "GND_2") (pintype "passive"))
      (node (ref "Y1") (pin "3") (pinfunction "OSC2_3") (pintype "passive"))
    )
    (net (code "96") (name "LCD_LED+") (class "Default")
      (node (ref "C75") (pin "1") (pintype "passive"))
      (node (ref "C76") (pin "1") (pintype "passive"))
      (node (ref "D3") (pin "1") (pinfunction "K_1") (pintype "passive"))
      (node (ref "J7") (pin "48") (pinfunction "LED+_48") (pintype "passive"))
      (node (ref "U9") (pin "5") (pinfunction "OVP_5") (pintype "passive"))
    )
    (net (code "97") (name "LCD_LED-") (class "Default")
      (node (ref "J7") (pin "47") (pinfunction "LED1-_47") (pintype "passive"))
      (node (ref "R39") (pin "2") (pintype "passive"))
      (node (ref "U9") (pin "3") (pinfunction "FB_3") (pintype "passive"))
    )
    (net (code "98") (name "LCD_VCCIO") (class "Default")
      (node (ref "C65") (pin "1") (pintype "passive"))
      (node (ref "C66") (pin "1") (pintype "passive"))
      (node (ref "C84") (pin "1") (pintype "passive"))
      (node (ref "J7") (pin "39") (pinfunction "VDDI_39") (pintype "passive"))
      (node (ref "J7") (pin "41") (pinfunction "VDDI_41") (pintype "passive"))
      (node (ref "J7") (pin "45") (pinfunction "ID1_45") (pintype "passive"))
      (node (ref "J7") (pin "46") (pinfunction "ID2_46") (pintype "passive"))
      (node (ref "R11") (pin "2") (pintype "passive"))
      (node (ref "U10") (pin "1") (pinfunction "VCCA_1") (pintype "passive"))
      (node (ref "U6") (pin "5") (pinfunction "VOUT_5") (pintype "passive"))
    )
    (net (code "99") (name "LCD_VSN") (class "Default")
      (node (ref "C68") (pin "1") (pintype "passive"))
      (node (ref "C69") (pin "1") (pintype "passive"))
      (node (ref "J7") (pin "3") (pinfunction "AVEE_3") (pintype "passive"))
      (node (ref "U7") (pin "2") (pinfunction "VN_2") (pintype "passive"))
    )
    (net (code "100") (name "LCD_VSP") (class "Default")
      (node (ref "C59") (pin "1") (pintype "passive"))
      (node (ref "C60") (pin "1") (pintype "passive"))
      (node (ref "J7") (pin "4") (pinfunction "AVDD_4") (pintype "passive"))
      (node (ref "U7") (pin "9") (pinfunction "VP_9") (pintype "passive"))
    )
    (net (code "101") (name "Net-(C27-Pad1)") (class "Default")
      (node (ref "C27") (pin "1") (pintype "passive"))
      (node (ref "C28") (pin "1") (pintype "passive"))
      (node (ref "C29") (pin "2") (pintype "passive"))
      (node (ref "FB5") (pin "1") (pinfunction "1_1") (pintype "passive"))
      (node (ref "FB6") (pin "1") (pinfunction "1_1") (pintype "passive"))
      (node (ref "FB7") (pin "1") (pinfunction "1_1") (pintype "passive"))
      (node (ref "FB8") (pin "1") (pinfunction "1_1") (pintype "passive"))
      (node (ref "L1") (pin "2") (pinfunction "2_2") (pintype "passive"))
      (node (ref "R32") (pin "1") (pintype "passive"))
    )
    (net (code "102") (name "Net-(C73-Pad2)") (class "Default")
      (node (ref "C73") (pin "2") (pintype "passive"))
      (node (ref "R35") (pin "1") (pintype "passive"))
      (node (ref "R36") (pin "2") (pintype "passive"))
    )
    (net (code "103") (name "Net-(C74-Pad2)") (class "Default")
      (node (ref "C74") (pin "2") (pintype "passive"))
      (node (ref "R37") (pin "1") (pintype "passive"))
      (node (ref "R38") (pin "2") (pintype "passive"))
    )
    (net (code "104") (name "Net-(D3-A)") (class "Default")
      (node (ref "D3") (pin "2") (pinfunction "A_2") (pintype "passive"))
      (node (ref "L2") (pin "2") (pinfunction "2_2") (pintype "passive"))
      (node (ref "U9") (pin "1") (pinfunction "SW_1") (pintype "passive"))
    )
    (net (code "105") (name "Net-(J1-CC1)") (class "Default")
      (node (ref "J1") (pin "A5") (pinfunction "CC1_A5") (pintype "passive"))
      (node (ref "R10") (pin "2") (pintype "passive"))
    )
    (net (code "106") (name "Net-(J1-CC2)") (class "Default")
      (node (ref "J1") (pin "B5") (pinfunction "CC2_B5") (pintype "passive"))
      (node (ref "R12") (pin "1") (pintype "passive"))
    )
    (net (code "107") (name "Net-(J1-SBU1)") (class "Default")
      (node (ref "C5") (pin "1") (pintype "passive"))
      (node (ref "J1") (pin "A8") (pinfunction "SBU1_A8") (pintype "passive"))
    )
    (net (code "108") (name "Net-(J1-SBU2)") (class "Default")
      (node (ref "C4") (pin "2") (pintype "passive"))
      (node (ref "J1") (pin "B8") (pinfunction "SBU2_B8") (pintype "passive"))
    )
    (net (code "109") (name "Net-(J7-LED2-)") (class "Default")
      (node (ref "J7") (pin "49") (pinfunction "LED2-_49") (pintype "passive"))
      (node (ref "R40") (pin "2") (pintype "passive"))
    )
    (net (code "110") (name "Net-(LED1-A)") (class "Default")
      (node (ref "LED1") (pin "1") (pinfunction "A_1") (pintype "passive"))
      (node (ref "R3") (pin "1") (pintype "passive"))
    )
    (net (code "111") (name "Net-(LED2-A)") (class "Default")
      (node (ref "LED2") (pin "1") (pinfunction "A_1") (pintype "passive"))
      (node (ref "R4") (pin "1") (pintype "passive"))
    )
    (net (code "112") (name "Net-(LED3-A)") (class "Default")
      (node (ref "LED3") (pin "1") (pinfunction "A_1") (pintype "passive"))
      (node (ref "R5") (pin "1") (pintype "passive"))
    )
    (net (code "113") (name "Net-(LED4-A)") (class "Default")
      (node (ref "LED4") (pin "1") (pinfunction "A_1") (pintype "passive"))
      (node (ref "R22") (pin "1") (pintype "passive"))
    )
    (net (code "114") (name "Net-(U1-EN)") (class "Default")
      (node (ref "R15") (pin "1") (pintype "passive"))
      (node (ref "U1") (pin "17") (pinfunction "EN_17") (pintype "passive"))
    )
    (net (code "115") (name "Net-(U2-BOOT0)") (class "Default")
      (node (ref "R23") (pin "2") (pintype "passive"))
      (node (ref "U2") (pin "44") (pinfunction "BOOT0_44") (pintype "power_in"))
    )
    (net (code "116") (name "Net-(U2-PB6)") (class "Default")
      (node (ref "R24") (pin "2") (pintype "passive"))
      (node (ref "U2") (pin "42") (pinfunction "PB6_42") (pintype "power_in"))
    )
    (net (code "117") (name "Net-(U2-PB7)") (class "Default")
      (node (ref "R25") (pin "2") (pintype "passive"))
      (node (ref "U2") (pin "43") (pinfunction "PB7_43") (pintype "power_in"))
    )
    (net (code "118") (name "Net-(U2-PB10)") (class "Default")
      (node (ref "R9") (pin "1") (pintype "passive"))
      (node (ref "U2") (pin "21") (pinfunction "PB10_21") (pintype "power_in"))
    )
    (net (code "119") (name "Net-(U2-PB11)") (class "Default")
      (node (ref "R8") (pin "1") (pintype "passive"))
      (node (ref "U2") (pin "22") (pinfunction "PB11_22") (pintype "power_in"))
    )
    (net (code "120") (name "Net-(U2-PF0{slash}OSC-IN)") (class "Default")
      (node (ref "U2") (pin "5") (pinfunction "PF0/OSC-IN_5") (pintype "power_in"))
      (node (ref "Y1") (pin "1") (pinfunction "OSC1_1") (pintype "passive"))
    )
    (net (code "121") (name "Net-(U2-PF1{slash}OSC-OUT)") (class "Default")
      (node (ref "U2") (pin "6") (pinfunction "PF1/OSC-OUT_6") (pintype "power_in"))
      (node (ref "Y1") (pin "2") (pinfunction "OSC2_2") (pintype "passive"))
    )
    (net (code "122") (name "Net-(U5-FB)") (class "Default")
      (node (ref "C29") (pin "1") (pintype "passive"))
      (node (ref "R32") (pin "2") (pintype "passive"))
      (node (ref "R33") (pin "2") (pintype "passive"))
      (node (ref "U5") (pin "5") (pinfunction "FB_5") (pintype "input"))
    )
    (net (code "123") (name "Net-(U5-RUN)") (class "Default")
      (node (ref "R31") (pin "2") (pintype "passive"))
      (node (ref "U5") (pin "1") (pinfunction "RUN_1") (pintype "input"))
    )
    (net (code "124") (name "Net-(U5-SW)") (class "Default")
      (node (ref "L1") (pin "1") (pinfunction "1_1") (pintype "passive"))
      (node (ref "U5") (pin "3") (pinfunction "SW_3") (pintype "passive"))
    )
    (net (code "125") (name "Net-(U7-C1N)") (class "Default")
      (node (ref "C62") (pin "2") (pintype "passive"))
      (node (ref "U7") (pin "4") (pinfunction "C1N_4") (pintype "passive"))
    )
    (net (code "126") (name "Net-(U7-C1P)") (class "Default")
      (node (ref "C62") (pin "1") (pintype "passive"))
      (node (ref "U7") (pin "3") (pinfunction "C1P_3") (pintype "passive"))
    )
    (net (code "127") (name "Net-(U7-C2N)") (class "Default")
      (node (ref "C61") (pin "2") (pintype "passive"))
      (node (ref "U7") (pin "7") (pinfunction "C2N_7") (pintype "passive"))
    )
    (net (code "128") (name "Net-(U7-C2P)") (class "Default")
      (node (ref "C61") (pin "1") (pintype "passive"))
      (node (ref "U7") (pin "8") (pinfunction "C2P_8") (pintype "passive"))
    )
    (net (code "129") (name "Net-(U7-C3N)") (class "Default")
      (node (ref "C67") (pin "2") (pintype "passive"))
      (node (ref "U7") (pin "10") (pinfunction "C3N_10") (pintype "passive"))
    )
    (net (code "130") (name "Net-(U7-C3P)") (class "Default")
      (node (ref "C67") (pin "1") (pintype "passive"))
      (node (ref "U7") (pin "1") (pinfunction "C3P_1") (pintype "passive"))
    )
    (net (code "131") (name "Net-(U8-AOUTL)") (class "Default")
      (node (ref "C74") (pin "1") (pintype "passive"))
      (node (ref "U8") (pin "7") (pinfunction "AOUTL_7") (pintype "passive"))
    )
    (net (code "132") (name "Net-(U8-AOUTR)") (class "Default")
      (node (ref "C73") (pin "1") (pintype "passive"))
      (node (ref "U8") (pin "10") (pinfunction "AOUTR_10") (pintype "passive"))
    )
    (net (code "133") (name "Net-(U8-FILT+)") (class "Default")
      (node (ref "C77") (pin "1") (pintype "passive"))
      (node (ref "U8") (pin "6") (pinfunction "FILT+_6") (pintype "input"))
    )
    (net (code "134") (name "Net-(U8-VQ)") (class "Default")
      (node (ref "C79") (pin "1") (pintype "passive"))
      (node (ref "C80") (pin "1") (pintype "passive"))
      (node (ref "U8") (pin "5") (pinfunction "VQ_5") (pintype "passive"))
    )
    (net (code "135") (name "Net-(U10-OE)") (class "Default")
      (node (ref "C85") (pin "1") (pintype "passive"))
      (node (ref "R11") (pin "1") (pintype "passive"))
      (node (ref "R17") (pin "2") (pintype "passive"))
      (node (ref "U10") (pin "8") (pinfunction "OE_8") (pintype "input"))
    )
    (net (code "136") (name "VBUS") (class "Default")
      (node (ref "D1") (pin "2") (pinfunction "A_2") (pintype "passive"))
      (node (ref "J1") (pin "A4") (pinfunction "VBUS_A4") (pintype "passive"))
      (node (ref "J1") (pin "A9") (pinfunction "VBUS_A9") (pintype "passive"))
      (node (ref "J1") (pin "B4") (pinfunction "VBUS_B4") (pintype "passive"))
      (node (ref "J1") (pin "B9") (pinfunction "VBUS_B9") (pintype "passive"))
      (node (ref "J8") (pin "1") (pinfunction "VBUS_1") (pintype "passive"))
    )
    (net (code "137") (name "VCC12A_RX") (class "Default")
      (node (ref "C48") (pin "1") (pintype "passive"))
      (node (ref "C49") (pin "1") (pintype "passive"))
      (node (ref "C50") (pin "1") (pintype "passive"))
      (node (ref "C51") (pin "1") (pintype "passive"))
      (node (ref "C52") (pin "1") (pintype "passive"))
      (node (ref "FB7") (pin "2") (pinfunction "2_2") (pintype "passive"))
      (node (ref "U4") (pin "10") (pinfunction "VCC12_PI_10") (pintype "power_in"))
      (node (ref "U4") (pin "13") (pinfunction "VCC12_RXPLL_13") (pintype "power_in"))
      (node (ref "U4") (pin "4") (pinfunction "VCC12A_RX_4") (pintype "power_in"))
    )
    (net (code "138") (name "VCC12D_RX") (class "Default")
      (node (ref "C45") (pin "1") (pintype "passive"))
      (node (ref "C46") (pin "1") (pintype "passive"))
      (node (ref "C47") (pin "1") (pintype "passive"))
      (node (ref "FB8") (pin "2") (pinfunction "2_2") (pintype "passive"))
      (node (ref "U4") (pin "1") (pinfunction "VCC12D_RX_1") (pintype "power_in"))
    )
    (net (code "139") (name "VCC12_TX") (class "Default")
      (node (ref "C53") (pin "1") (pintype "passive"))
      (node (ref "C54") (pin "1") (pintype "passive"))
      (node (ref "C55") (pin "1") (pintype "passive"))
      (node (ref "C56") (pin "1") (pintype "passive"))
      (node (ref "C57") (pin "1") (pintype "passive"))
      (node (ref "FB6") (pin "2") (pinfunction "2_2") (pintype "passive"))
      (node (ref "U4") (pin "34") (pinfunction "VCC12_TX_34") (pintype "power_in"))
      (node (ref "U4") (pin "46") (pinfunction "VCC12_TX2_46") (pintype "power_in"))
      (node (ref "U4") (pin "48") (pinfunction "VCC12_TX1_48") (pintype "power_in"))
      (node (ref "U4") (pin "59") (pinfunction "VCC12_TX0_59") (pintype "power_in"))
    )
    (net (code "140") (name "VCC33") (class "Default")
      (node (ref "C16") (pin "1") (pintype "passive"))
      (node (ref "C17") (pin "1") (pintype "passive"))
      (node (ref "C18") (pin "1") (pintype "passive"))
      (node (ref "C58") (pin "1") (pintype "passive"))
      (node (ref "C63") (pin "1") (pintype "passive"))
      (node (ref "C64") (pin "1") (pintype "passive"))
      (node (ref "C70") (pin "1") (pintype "passive"))
      (node (ref "C71") (pin "1") (pintype "passive"))
      (node (ref "C83") (pin "1") (pintype "passive"))
      (node (ref "FB1") (pin "1") (pinfunction "1_1") (pintype "passive"))
      (node (ref "FB2") (pin "1") (pinfunction "1_1") (pintype "passive"))
      (node (ref "FB3") (pin "1") (pinfunction "1_1") (pintype "passive"))
      (node (ref "FB4") (pin "1") (pinfunction "1_1") (pintype "passive"))
      (node (ref "R26") (pin "2") (pintype "passive"))
      (node (ref "R31") (pin "1") (pintype "passive"))
      (node (ref "U10") (pin "14") (pinfunction "VCCB_14") (pintype "passive"))
      (node (ref "U3") (pin "2") (pinfunction "OUT_2") (pintype "passive"))
      (node (ref "U3") (pin "4") (pinfunction "OUT_4") (pintype "passive"))
      (node (ref "U6") (pin "1") (pinfunction "VIN_1") (pintype "passive"))
      (node (ref "U7") (pin "6") (pinfunction "VIN_6") (pintype "passive"))
      (node (ref "U8") (pin "9") (pinfunction "VA_9") (pintype "passive"))
    )
    (net (code "141") (name "VCC33_HD3") (class "Default")
      (node (ref "C9") (pin "1") (pintype "passive"))
      (node (ref "FB4") (pin "2") (pinfunction "2_2") (pintype "passive"))
      (node (ref "R15") (pin "2") (pintype "passive"))
      (node (ref "R18") (pin "2") (pintype "passive"))
      (node (ref "U1") (pin "22") (pinfunction "VCC_22") (pintype "passive"))
    )
    (net (code "142") (name "VCC33_RX") (class "Default")
      (node (ref "C36") (pin "1") (pintype "passive"))
      (node (ref "C37") (pin "1") (pintype "passive"))
      (node (ref "C38") (pin "1") (pintype "passive"))
      (node (ref "C39") (pin "1") (pintype "passive"))
      (node (ref "FB3") (pin "2") (pinfunction "2_2") (pintype "passive"))
      (node (ref "U4") (pin "62") (pinfunction "VCC33_BG_62") (pintype "power_in"))
      (node (ref "U4") (pin "7") (pinfunction "VCC33_RX_7") (pintype "power_in"))
    )
    (net (code "143") (name "VCC33_STM") (class "Default")
      (node (ref "C1") (pin "2") (pintype "passive"))
      (node (ref "C10") (pin "2") (pintype "passive"))
      (node (ref "C13") (pin "2") (pintype "passive"))
      (node (ref "C8") (pin "1") (pintype "passive"))
      (node (ref "FB1") (pin "2") (pinfunction "2_2") (pintype "passive"))
      (node (ref "J2") (pin "1") (pinfunction "1_1") (pintype "passive"))
      (node (ref "J3") (pin "1") (pinfunction "1_1") (pintype "passive"))
      (node (ref "R1") (pin "2") (pintype "passive"))
      (node (ref "R19") (pin "2") (pintype "passive"))
      (node (ref "R2") (pin "2") (pintype "passive"))
      (node (ref "R20") (pin "2") (pintype "passive"))
      (node (ref "R21") (pin "2") (pintype "passive"))
      (node (ref "R29") (pin "2") (pintype "passive"))
      (node (ref "R30") (pin "2") (pintype "passive"))
      (node (ref "U2") (pin "1") (pinfunction "VBAT_1") (pintype "power_in"))
      (node (ref "U2") (pin "24") (pinfunction "VDD1_24") (pintype "power_in"))
      (node (ref "U2") (pin "36") (pinfunction "VDD2_36") (pintype "power_in"))
      (node (ref "U2") (pin "48") (pinfunction "VDD_48") (pintype "power_in"))
      (node (ref "U2") (pin "9") (pinfunction "VDDA/VREF+_9") (pintype "power_in"))
    )
    (net (code "144") (name "VCC33_TX") (class "Default")
      (node (ref "C30") (pin "1") (pintype "passive"))
      (node (ref "C31") (pin "1") (pintype "passive"))
      (node (ref "C32") (pin "1") (pintype "passive"))
      (node (ref "C33") (pin "1") (pintype "passive"))
      (node (ref "C34") (pin "1") (pintype "passive"))
      (node (ref "C35") (pin "1") (pintype "passive"))
      (node (ref "FB2") (pin "2") (pinfunction "2_2") (pintype "passive"))
      (node (ref "U4") (pin "16") (pinfunction "VCC33_IO_16") (pintype "power_in"))
      (node (ref "U4") (pin "25") (pinfunction "VCC33_IO_25") (pintype "power_in"))
      (node (ref "U4") (pin "33") (pinfunction "VCC33_TX_33") (pintype "power_in"))
      (node (ref "U4") (pin "45") (pinfunction "VCC33_TX2_45") (pintype "power_in"))
      (node (ref "U4") (pin "47") (pinfunction "VCC33_TXPLL_47") (pintype "power_in"))
    )
    (net (code "145") (name "VDD") (class "Default")
      (node (ref "C40") (pin "1") (pintype "passive"))
      (node (ref "C41") (pin "1") (pintype "passive"))
      (node (ref "C42") (pin "1") (pintype "passive"))
      (node (ref "C43") (pin "1") (pintype "passive"))
      (node (ref "C44") (pin "1") (pintype "passive"))
      (node (ref "FB5") (pin "2") (pinfunction "2_2") (pintype "passive"))
      (node (ref "U4") (pin "24") (pinfunction "VDD_24") (pintype "power_in"))
      (node (ref "U4") (pin "30") (pinfunction "VDD_30") (pintype "power_in"))
      (node (ref "U4") (pin "60") (pinfunction "VDD_60") (pintype "power_in"))
    )
    (net (code "146") (name "unconnected-(J1-NC1-Pad5)") (class "Default")
      (node (ref "J1") (pin "5") (pinfunction "NC1_5") (pintype "passive"))
    )
    (net (code "147") (name "unconnected-(J1-NC2-Pad6)") (class "Default")
      (node (ref "J1") (pin "6") (pinfunction "NC2_6") (pintype "passive"))
    )
    (net (code "148") (name "unconnected-(J2-Pad5)") (class "Default")
      (node (ref "J2") (pin "5") (pinfunction "5_5") (pintype "passive"))
    )
    (net (code "149") (name "unconnected-(J2-Pad6)") (class "Default")
      (node (ref "J2") (pin "6") (pinfunction "6_6") (pintype "passive"))
    )
    (net (code "150") (name "unconnected-(J6-Pad3)") (class "Default")
      (node (ref "J6") (pin "3") (pintype "passive"))
    )
    (net (code "151") (name "unconnected-(J6-Pad4)") (class "Default")
      (node (ref "J6") (pin "4") (pintype "passive"))
    )
    (net (code "152") (name "unconnected-(J7-NC-Pad50)") (class "Default")
      (node (ref "J7") (pin "50") (pinfunction "NC_50") (pintype "passive"))
    )
    (net (code "153") (name "unconnected-(J8-D+-Pad3)") (class "Default")
      (node (ref "J8") (pin "3") (pinfunction "D+_3") (pintype "passive"))
    )
    (net (code "154") (name "unconnected-(J8-D--Pad2)") (class "Default")
      (node (ref "J8") (pin "2") (pinfunction "D-_2") (pintype "passive"))
    )
    (net (code "155") (name "unconnected-(U2-PA10-Pad31)") (class "Default")
      (node (ref "U2") (pin "31") (pinfunction "PA10_31") (pintype "power_in"))
    )
    (net (code "156") (name "unconnected-(U2-PA15-Pad38)") (class "Default")
      (node (ref "U2") (pin "38") (pinfunction "PA15_38") (pintype "power_in"))
    )
    (net (code "157") (name "unconnected-(U2-PB0-Pad18)") (class "Default")
      (node (ref "U2") (pin "18") (pinfunction "PB0_18") (pintype "power_in"))
    )
    (net (code "158") (name "unconnected-(U2-PB3-Pad39)") (class "Default")
      (node (ref "U2") (pin "39") (pinfunction "PB3_39") (pintype "power_in"))
    )
    (net (code "159") (name "unconnected-(U2-PB4-Pad40)") (class "Default")
      (node (ref "U2") (pin "40") (pinfunction "PB4_40") (pintype "power_in"))
    )
    (net (code "160") (name "unconnected-(U2-PB5-Pad41)") (class "Default")
      (node (ref "U2") (pin "41") (pinfunction "PB5_41") (pintype "power_in"))
    )
    (net (code "161") (name "unconnected-(U2-PB8-Pad45)") (class "Default")
      (node (ref "U2") (pin "45") (pinfunction "PB8_45") (pintype "power_in"))
    )
    (net (code "162") (name "unconnected-(U2-PB9-Pad46)") (class "Default")
      (node (ref "U2") (pin "46") (pinfunction "PB9_46") (pintype "power_in"))
    )
    (net (code "163") (name "unconnected-(U2-PB13-Pad26)") (class "Default")
      (node (ref "U2") (pin "26") (pinfunction "PB13_26") (pintype "power_in"))
    )
    (net (code "164") (name "unconnected-(U2-PC15-Pad4)") (class "Default")
      (node (ref "U2") (pin "4") (pinfunction "PC15_4") (pintype "power_in"))
    )
    (net (code "165") (name "unconnected-(U4-RX_HPD-Pad23)") (class "Default")
      (node (ref "U4") (pin "23") (pinfunction "RX_HPD_23") (pintype "output"))
    )
    (net (code "166") (name "unconnected-(U6-NC-Pad4)") (class "Default")
      (node (ref "U6") (pin "4") (pinfunction "NC_4") (pintype "passive"))
    )
    (net (code "167") (name "unconnected-(U10-NC-Pad6)") (class "Default")
      (node (ref "U10") (pin "6") (pinfunction "NC_6") (pintype "input+no_connect"))
    )
    (net (code "168") (name "unconnected-(U10-NC-Pad9)") (class "Default")
      (node (ref "U10") (pin "9") (pinfunction "NC_9") (pintype "passive+no_connect"))
    )
  )
)
